# 20230822.net
KiCad netlist of a schematic drawn in EAGLE
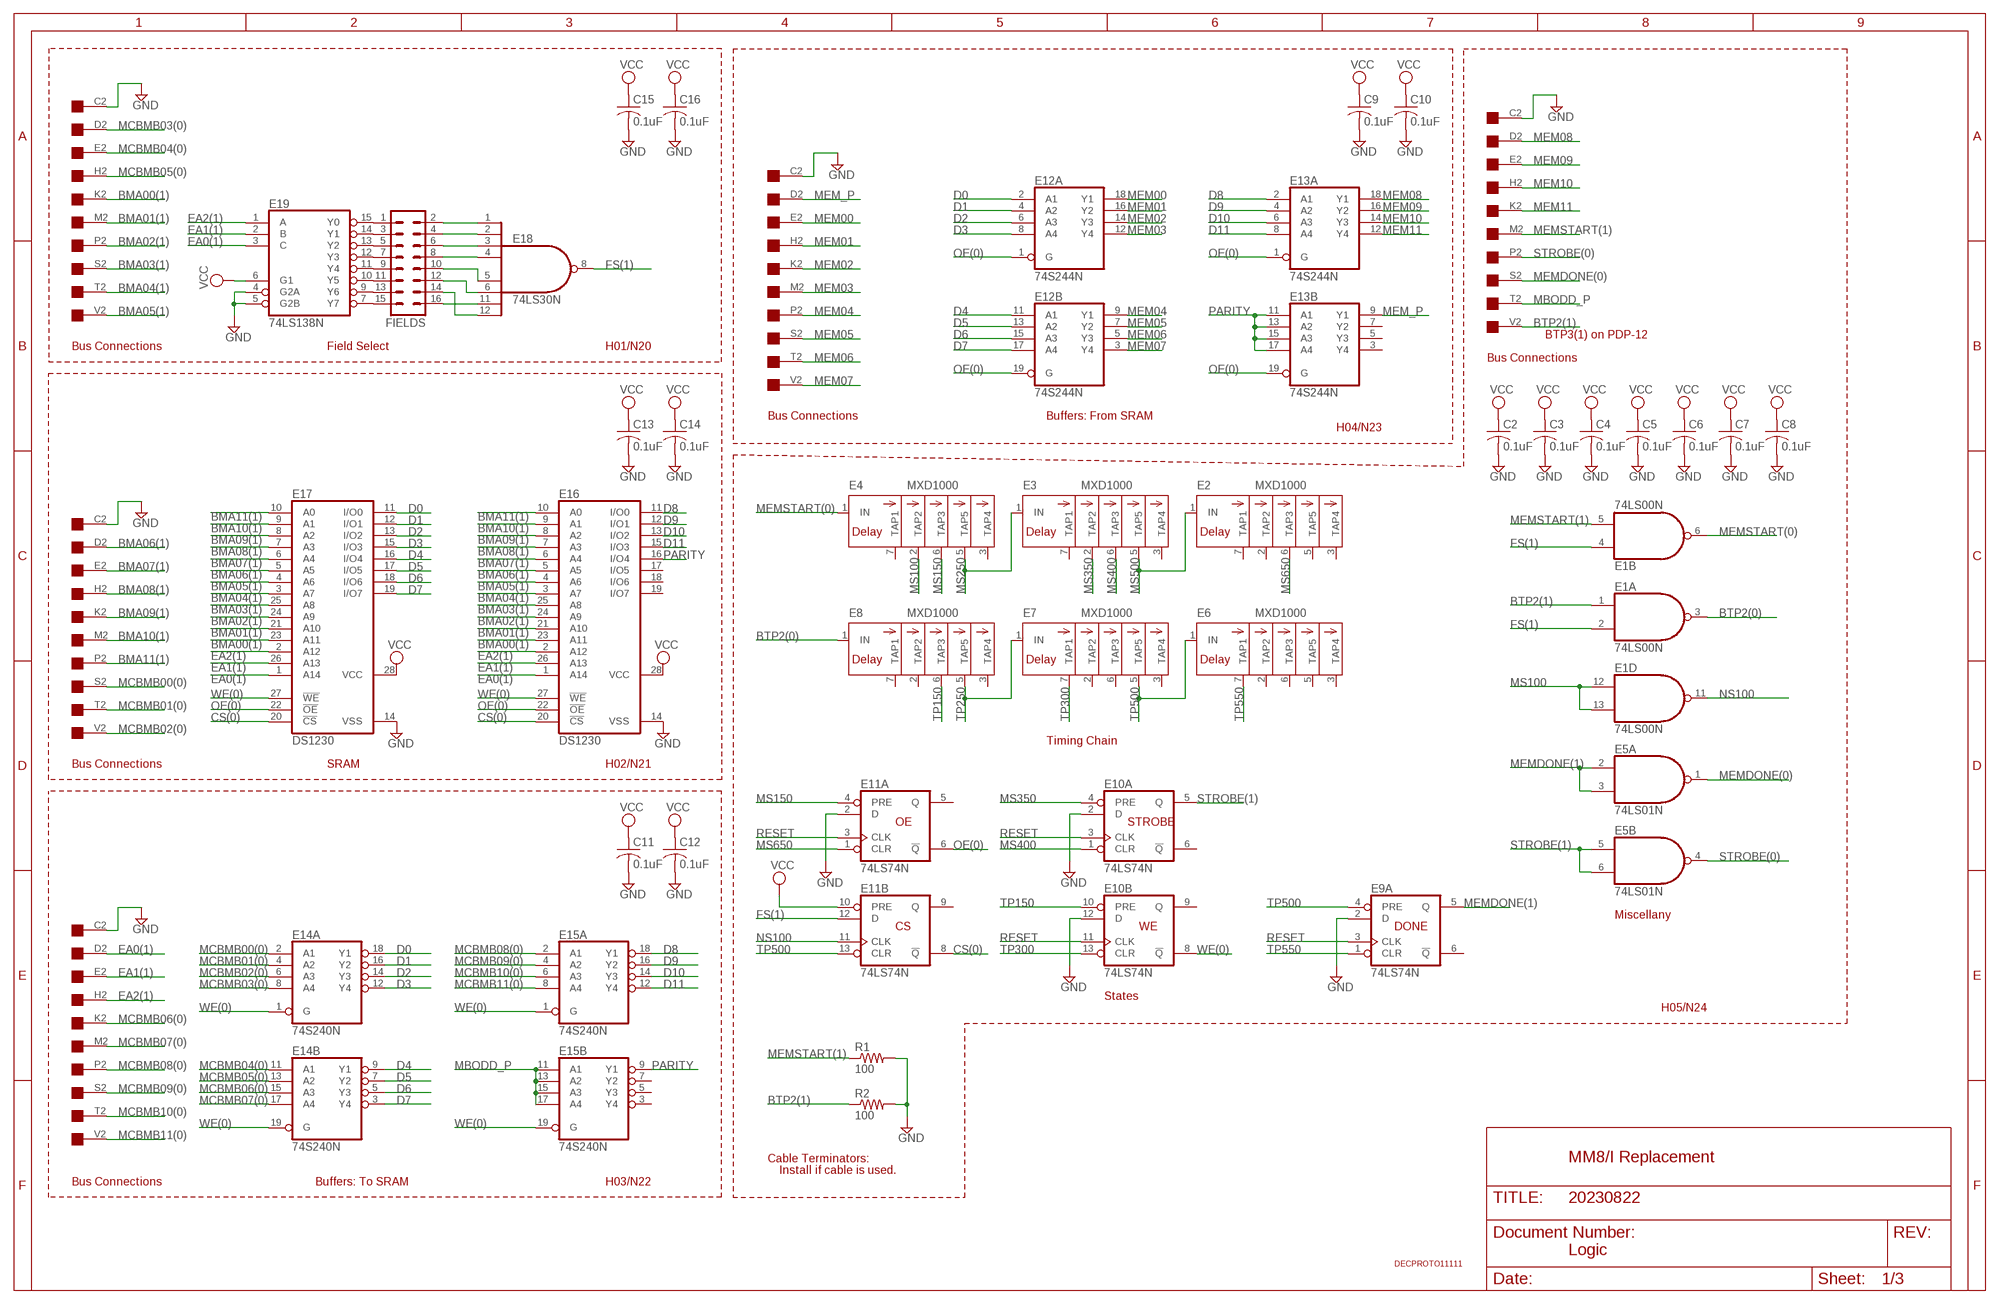
[diagram p0: schematic, sheet 1]
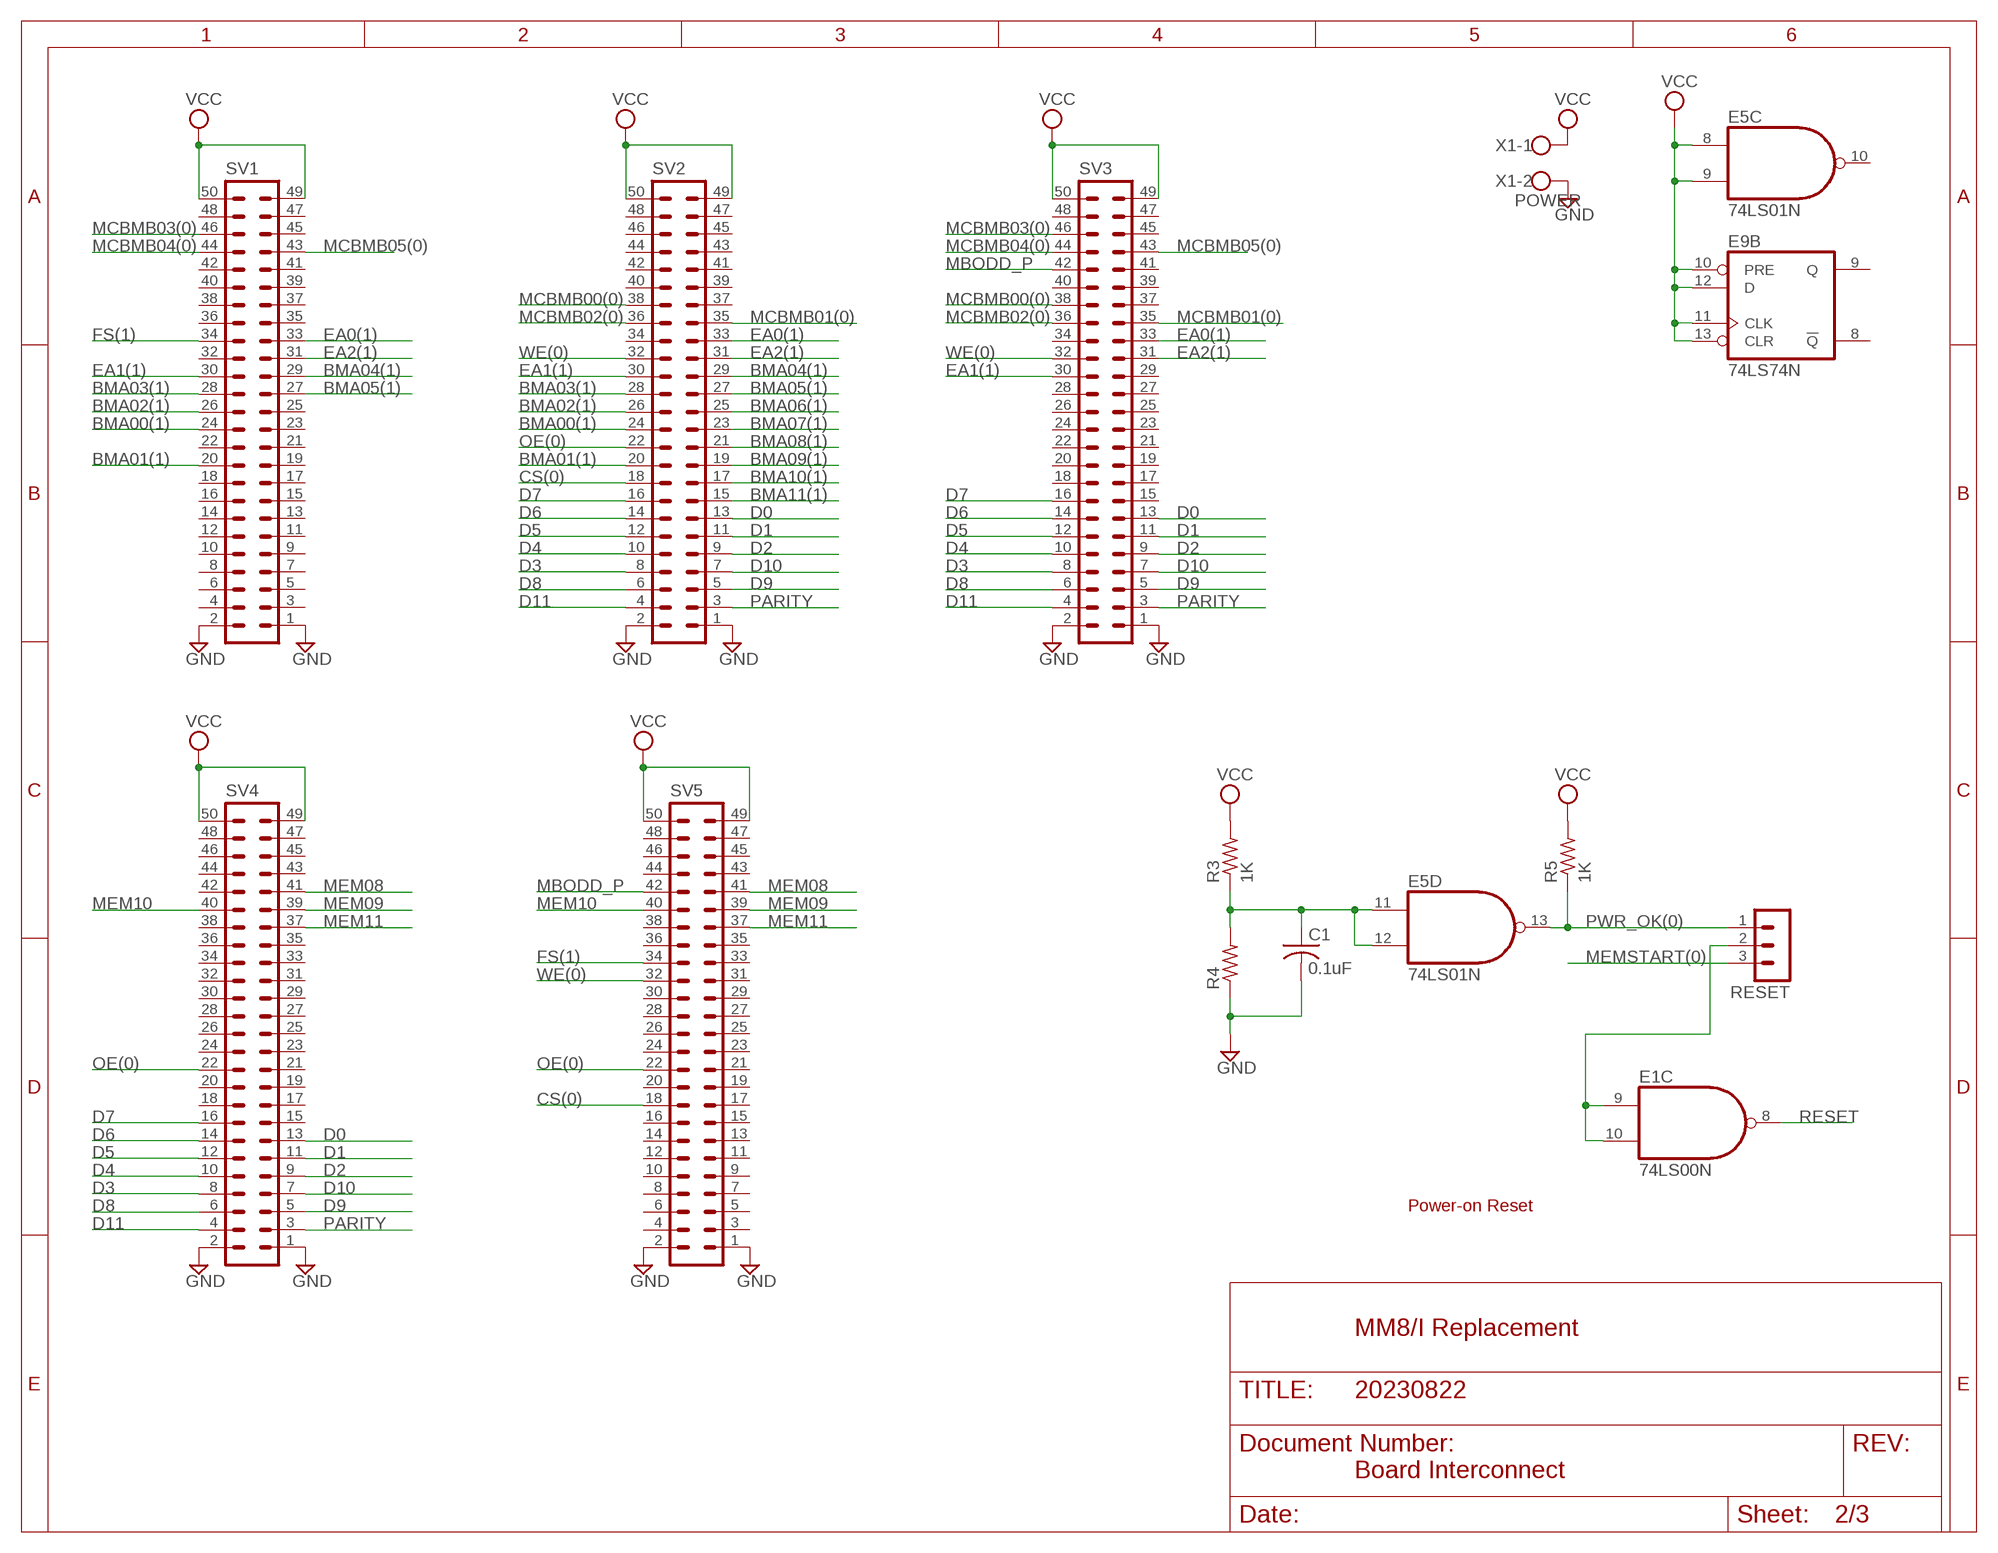
[diagram p1: schematic, sheet 2]
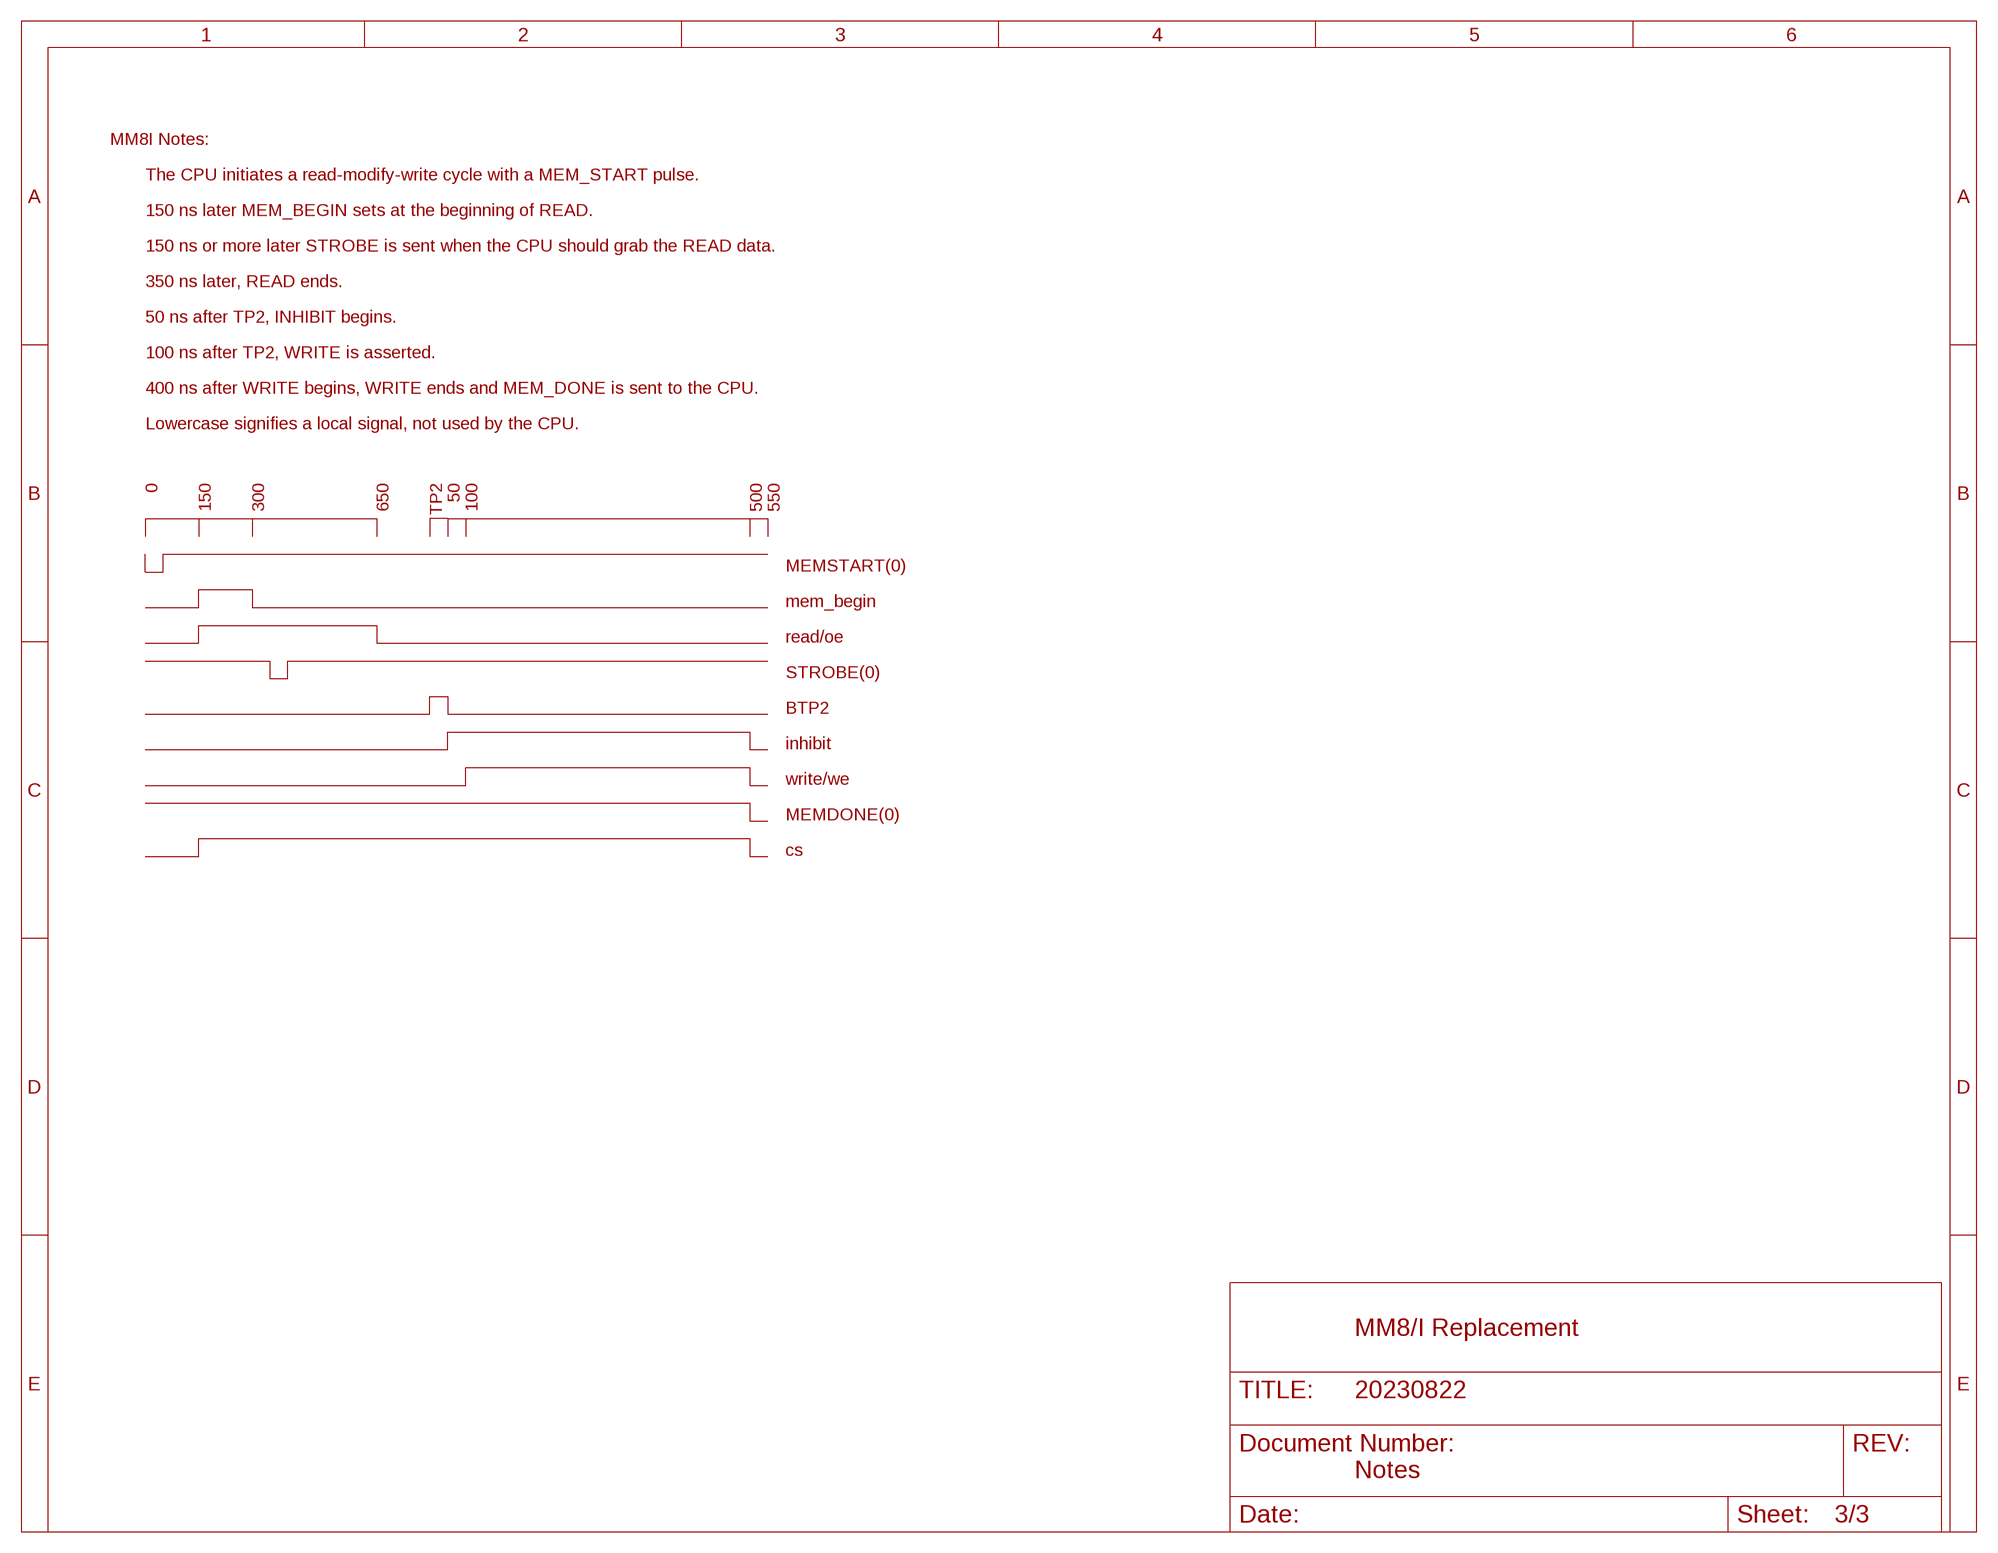
[diagram p2: schematic, sheet 3]

(export (version "E")
  (design (tool "Eeschema 10.0.6"))
  (components
    (comp (ref "C1")
      (value "0.1uF")
      (footprint "eagle-import:C050-025X075")
      (libsource (lib "eagle-import") (part "C-US050-025X075"))
    )
    (comp (ref "E1")
      (value "74LS00N")
      (footprint "eagle-import:DIL14")
      (libsource (lib "eagle-import") (part "7400NLS"))
    )
    (comp (ref "E5")
      (value "74LS01N")
      (footprint "eagle-import:DIL14")
      (libsource (lib "eagle-import") (part "7401NLS"))
    )
    (comp (ref "E9")
      (value "74LS74N")
      (footprint "eagle-import:DIL14")
      (libsource (lib "eagle-import") (part "7474NLS"))
    )
    (comp (ref "R3")
      (value "1K")
      (footprint "eagle-import:0207_10")
      (libsource (lib "eagle-import") (part "R-US_0207/10"))
    )
    (comp (ref "R4")
      (value "R-US_0207/10")
      (footprint "eagle-import:0207_10")
      (libsource (lib "eagle-import") (part "R-US_0207/10"))
    )
    (comp (ref "R5")
      (value "1K")
      (footprint "eagle-import:0207_10")
      (libsource (lib "eagle-import") (part "R-US_0207/10"))
    )
    (comp (ref "RESET")
      (value "MA03-1")
      (footprint "eagle-import:MA03-1")
      (libsource (lib "eagle-import") (part "MA03-1"))
    )
    (comp (ref "SV1")
      (value "ML50L")
      (footprint "eagle-import:ML50L")
      (libsource (lib "eagle-import") (part "ML50L"))
    )
    (comp (ref "SV2")
      (value "ML50L")
      (footprint "eagle-import:ML50L")
      (libsource (lib "eagle-import") (part "ML50L"))
    )
    (comp (ref "SV3")
      (value "ML50L")
      (footprint "eagle-import:ML50L")
      (libsource (lib "eagle-import") (part "ML50L"))
    )
    (comp (ref "SV4")
      (value "ML50L")
      (footprint "eagle-import:ML50L")
      (libsource (lib "eagle-import") (part "ML50L"))
    )
    (comp (ref "SV5")
      (value "ML50L")
      (footprint "eagle-import:ML50L")
      (libsource (lib "eagle-import") (part "ML50L"))
    )
    (comp (ref "X1")
      (value "POWER")
      (footprint "eagle-import:W237-102")
      (fields (field (name "MPN") "237-102"))
      (libsource (lib "eagle-import") (part "W237-102"))
    )
    (comp (ref "C2")
      (value "0.1uF")
      (footprint "eagle-import:C050-025X075")
      (libsource (lib "eagle-import") (part "C-US050-025X075"))
    )
    (comp (ref "C3")
      (value "0.1uF")
      (footprint "eagle-import:C050-025X075")
      (libsource (lib "eagle-import") (part "C-US050-025X075"))
    )
    (comp (ref "C4")
      (value "0.1uF")
      (footprint "eagle-import:C050-025X075")
      (libsource (lib "eagle-import") (part "C-US050-025X075"))
    )
    (comp (ref "C5")
      (value "0.1uF")
      (footprint "eagle-import:C050-025X075")
      (libsource (lib "eagle-import") (part "C-US050-025X075"))
    )
    (comp (ref "C6")
      (value "0.1uF")
      (footprint "eagle-import:C050-025X075")
      (libsource (lib "eagle-import") (part "C-US050-025X075"))
    )
    (comp (ref "C7")
      (value "0.1uF")
      (footprint "eagle-import:C050-025X075")
      (libsource (lib "eagle-import") (part "C-US050-025X075"))
    )
    (comp (ref "C8")
      (value "0.1uF")
      (footprint "eagle-import:C050-025X075")
      (libsource (lib "eagle-import") (part "C-US050-025X075"))
    )
    (comp (ref "C9")
      (value "0.1uF")
      (footprint "eagle-import:C050-025X075")
      (libsource (lib "eagle-import") (part "C-US050-025X075"))
    )
    (comp (ref "C10")
      (value "0.1uF")
      (footprint "eagle-import:C050-025X075")
      (libsource (lib "eagle-import") (part "C-US050-025X075"))
    )
    (comp (ref "C11")
      (value "0.1uF")
      (footprint "eagle-import:C050-025X075")
      (libsource (lib "eagle-import") (part "C-US050-025X075"))
    )
    (comp (ref "C12")
      (value "0.1uF")
      (footprint "eagle-import:C050-025X075")
      (libsource (lib "eagle-import") (part "C-US050-025X075"))
    )
    (comp (ref "C13")
      (value "0.1uF")
      (footprint "eagle-import:C050-025X075")
      (libsource (lib "eagle-import") (part "C-US050-025X075"))
    )
    (comp (ref "C14")
      (value "0.1uF")
      (footprint "eagle-import:C050-025X075")
      (libsource (lib "eagle-import") (part "C-US050-025X075"))
    )
    (comp (ref "C15")
      (value "0.1uF")
      (footprint "eagle-import:C050-025X075")
      (libsource (lib "eagle-import") (part "C-US050-025X075"))
    )
    (comp (ref "C16")
      (value "0.1uF")
      (footprint "eagle-import:C050-025X075")
      (libsource (lib "eagle-import") (part "C-US050-025X075"))
    )
    (comp (ref "E2")
      (value "MXD1000")
      (footprint "eagle-import:DIL08")
      (libsource (lib "eagle-import") (part "MXD1000"))
    )
    (comp (ref "E3")
      (value "MXD1000")
      (footprint "eagle-import:DIL08")
      (libsource (lib "eagle-import") (part "MXD1000"))
    )
    (comp (ref "E4")
      (value "MXD1000")
      (footprint "eagle-import:DIL08")
      (libsource (lib "eagle-import") (part "MXD1000"))
    )
    (comp (ref "E6")
      (value "MXD1000")
      (footprint "eagle-import:DIL08")
      (libsource (lib "eagle-import") (part "MXD1000"))
    )
    (comp (ref "E7")
      (value "MXD1000")
      (footprint "eagle-import:DIL08")
      (libsource (lib "eagle-import") (part "MXD1000"))
    )
    (comp (ref "E8")
      (value "MXD1000")
      (footprint "eagle-import:DIL08")
      (libsource (lib "eagle-import") (part "MXD1000"))
    )
    (comp (ref "E10")
      (value "74LS74N")
      (footprint "eagle-import:DIL14")
      (libsource (lib "eagle-import") (part "7474NLS"))
    )
    (comp (ref "E11")
      (value "74LS74N")
      (footprint "eagle-import:DIL14")
      (libsource (lib "eagle-import") (part "7474NLS"))
    )
    (comp (ref "E12")
      (value "74S244N")
      (footprint "eagle-import:DIL20")
      (libsource (lib "eagle-import") (part "74244NS"))
    )
    (comp (ref "E13")
      (value "74S244N")
      (footprint "eagle-import:DIL20")
      (libsource (lib "eagle-import") (part "74244NS"))
    )
    (comp (ref "E14")
      (value "74S240N")
      (footprint "eagle-import:DIL20")
      (libsource (lib "eagle-import") (part "74240NS"))
    )
    (comp (ref "E15")
      (value "74S240N")
      (footprint "eagle-import:DIL20")
      (libsource (lib "eagle-import") (part "74240NS"))
    )
    (comp (ref "E16")
      (value "DS1230")
      (footprint "eagle-import:DIL28-6")
      (libsource (lib "eagle-import") (part "62256P"))
    )
    (comp (ref "E17")
      (value "DS1230")
      (footprint "eagle-import:DIL28-6")
      (libsource (lib "eagle-import") (part "62256P"))
    )
    (comp (ref "E18")
      (value "74LS30N")
      (footprint "eagle-import:DIL14")
      (libsource (lib "eagle-import") (part "7430NLS"))
    )
    (comp (ref "E19")
      (value "74LS138N")
      (footprint "eagle-import:DIL16")
      (libsource (lib "eagle-import") (part "74138NLS"))
    )
    (comp (ref "FIELDS")
      (value "MA08-2")
      (footprint "eagle-import:MA08-2")
      (libsource (lib "eagle-import") (part "MA08-2"))
    )
    (comp (ref "H01")
      (value "EDGE-1")
      (footprint "eagle-import:EDGE-CON1")
      (libsource (lib "eagle-import") (part "EDGE-1"))
    )
    (comp (ref "H02")
      (value "EDGE-1")
      (footprint "eagle-import:EDGE-CON1")
      (libsource (lib "eagle-import") (part "EDGE-1"))
    )
    (comp (ref "H03")
      (value "EDGE-1")
      (footprint "eagle-import:EDGE-CON1")
      (libsource (lib "eagle-import") (part "EDGE-1"))
    )
    (comp (ref "H04")
      (value "EDGE-1")
      (footprint "eagle-import:EDGE-CON1")
      (libsource (lib "eagle-import") (part "EDGE-1"))
    )
    (comp (ref "H05")
      (value "EDGE-1")
      (footprint "eagle-import:EDGE-CON1")
      (libsource (lib "eagle-import") (part "EDGE-1"))
    )
    (comp (ref "R1")
      (value "100")
      (footprint "eagle-import:0207_10")
      (libsource (lib "eagle-import") (part "R-US_0207/10"))
    )
    (comp (ref "R2")
      (value "100")
      (footprint "eagle-import:0207_10")
      (libsource (lib "eagle-import") (part "R-US_0207/10"))
    )
    (comp (ref "U$6")
      (value "DECPROTO11111")
      (footprint "eagle-import:DECPROTO11111")
      (libsource (lib "eagle-import") (part "DECPROTO11111"))
    )
  )
  (nets
    (net (code "1") (name "BMA00(1)") (class "Default")
      (node (ref "E16") (pin "23") (pinfunction "A11_23") (pintype "input"))
      (node (ref "E17") (pin "23") (pinfunction "A11_23") (pintype "input"))
      (node (ref "H01") (pin "K2") (pinfunction "1_K2") (pintype "bidirectional"))
      (node (ref "SV1") (pin "24") (pinfunction "24_24") (pintype "passive"))
      (node (ref "SV2") (pin "24") (pinfunction "24_24") (pintype "passive"))
    )
    (net (code "2") (name "BMA01(1)") (class "Default")
      (node (ref "E16") (pin "21") (pinfunction "A10_21") (pintype "input"))
      (node (ref "E17") (pin "21") (pinfunction "A10_21") (pintype "input"))
      (node (ref "H01") (pin "M2") (pinfunction "1_M2") (pintype "bidirectional"))
      (node (ref "SV1") (pin "20") (pinfunction "20_20") (pintype "passive"))
      (node (ref "SV2") (pin "20") (pinfunction "20_20") (pintype "passive"))
    )
    (net (code "3") (name "BMA02(1)") (class "Default")
      (node (ref "E16") (pin "24") (pinfunction "A9_24") (pintype "input"))
      (node (ref "E17") (pin "24") (pinfunction "A9_24") (pintype "input"))
      (node (ref "H01") (pin "P2") (pinfunction "1_P2") (pintype "bidirectional"))
      (node (ref "SV1") (pin "26") (pinfunction "26_26") (pintype "passive"))
      (node (ref "SV2") (pin "26") (pinfunction "26_26") (pintype "passive"))
    )
    (net (code "4") (name "BMA03(1)") (class "Default")
      (node (ref "E16") (pin "25") (pinfunction "A8_25") (pintype "input"))
      (node (ref "E17") (pin "25") (pinfunction "A8_25") (pintype "input"))
      (node (ref "H01") (pin "S2") (pinfunction "1_S2") (pintype "bidirectional"))
      (node (ref "SV1") (pin "28") (pinfunction "28_28") (pintype "passive"))
      (node (ref "SV2") (pin "28") (pinfunction "28_28") (pintype "passive"))
    )
    (net (code "5") (name "BMA04(1)") (class "Default")
      (node (ref "E16") (pin "3") (pinfunction "A7_3") (pintype "input"))
      (node (ref "E17") (pin "3") (pinfunction "A7_3") (pintype "input"))
      (node (ref "H01") (pin "T2") (pinfunction "1_T2") (pintype "bidirectional"))
      (node (ref "SV1") (pin "29") (pinfunction "29_29") (pintype "passive"))
      (node (ref "SV2") (pin "29") (pinfunction "29_29") (pintype "passive"))
    )
    (net (code "6") (name "BMA05(1)") (class "Default")
      (node (ref "E16") (pin "4") (pinfunction "A6_4") (pintype "input"))
      (node (ref "E17") (pin "4") (pinfunction "A6_4") (pintype "input"))
      (node (ref "H01") (pin "V2") (pinfunction "1_V2") (pintype "bidirectional"))
      (node (ref "SV1") (pin "27") (pinfunction "27_27") (pintype "passive"))
      (node (ref "SV2") (pin "27") (pinfunction "27_27") (pintype "passive"))
    )
    (net (code "7") (name "BMA06(1)") (class "Default")
      (node (ref "E16") (pin "5") (pinfunction "A5_5") (pintype "input"))
      (node (ref "E17") (pin "5") (pinfunction "A5_5") (pintype "input"))
      (node (ref "H02") (pin "D2") (pinfunction "1_D2") (pintype "bidirectional"))
      (node (ref "SV2") (pin "25") (pinfunction "25_25") (pintype "passive"))
    )
    (net (code "8") (name "BMA07(1)") (class "Default")
      (node (ref "E16") (pin "6") (pinfunction "A4_6") (pintype "input"))
      (node (ref "E17") (pin "6") (pinfunction "A4_6") (pintype "input"))
      (node (ref "H02") (pin "E2") (pinfunction "1_E2") (pintype "bidirectional"))
      (node (ref "SV2") (pin "23") (pinfunction "23_23") (pintype "passive"))
    )
    (net (code "9") (name "BMA08(1)") (class "Default")
      (node (ref "E16") (pin "7") (pinfunction "A3_7") (pintype "input"))
      (node (ref "E17") (pin "7") (pinfunction "A3_7") (pintype "input"))
      (node (ref "H02") (pin "H2") (pinfunction "1_H2") (pintype "bidirectional"))
      (node (ref "SV2") (pin "21") (pinfunction "21_21") (pintype "passive"))
    )
    (net (code "10") (name "BMA09(1)") (class "Default")
      (node (ref "E16") (pin "8") (pinfunction "A2_8") (pintype "input"))
      (node (ref "E17") (pin "8") (pinfunction "A2_8") (pintype "input"))
      (node (ref "H02") (pin "K2") (pinfunction "1_K2") (pintype "bidirectional"))
      (node (ref "SV2") (pin "19") (pinfunction "19_19") (pintype "passive"))
    )
    (net (code "11") (name "BMA10(1)") (class "Default")
      (node (ref "E16") (pin "9") (pinfunction "A1_9") (pintype "input"))
      (node (ref "E17") (pin "9") (pinfunction "A1_9") (pintype "input"))
      (node (ref "H02") (pin "M2") (pinfunction "1_M2") (pintype "bidirectional"))
      (node (ref "SV2") (pin "17") (pinfunction "17_17") (pintype "passive"))
    )
    (net (code "12") (name "BMA11(1)") (class "Default")
      (node (ref "E16") (pin "10") (pinfunction "A0_10") (pintype "input"))
      (node (ref "E17") (pin "10") (pinfunction "A0_10") (pintype "input"))
      (node (ref "H02") (pin "P2") (pinfunction "1_P2") (pintype "bidirectional"))
      (node (ref "SV2") (pin "15") (pinfunction "15_15") (pintype "passive"))
    )
    (net (code "13") (name "BTP2(0)") (class "Default")
      (node (ref "E1") (pin "3") (pinfunction "O_3") (pintype "output"))
      (node (ref "E8") (pin "1") (pinfunction "IN_1") (pintype "input"))
    )
    (net (code "14") (name "BTP2(1)") (class "Default")
      (node (ref "E1") (pin "1") (pinfunction "I0_1") (pintype "input"))
      (node (ref "H05") (pin "V2") (pinfunction "1_V2") (pintype "bidirectional"))
      (node (ref "R2") (pin "1") (pinfunction "1_1") (pintype "passive"))
    )
    (net (code "15") (name "CS(0)") (class "Default")
      (node (ref "E11") (pin "8") (pinfunction "~{Q}_8") (pintype "output"))
      (node (ref "E16") (pin "20") (pinfunction "~{CS}_20") (pintype "input"))
      (node (ref "E17") (pin "20") (pinfunction "~{CS}_20") (pintype "input"))
      (node (ref "SV2") (pin "18") (pinfunction "18_18") (pintype "passive"))
      (node (ref "SV5") (pin "18") (pinfunction "18_18") (pintype "passive"))
    )
    (net (code "16") (name "D0") (class "Default")
      (node (ref "E12") (pin "2") (pinfunction "A1_2") (pintype "input"))
      (node (ref "E14") (pin "18") (pinfunction "Y1_18") (pintype "tri_state"))
      (node (ref "E17") (pin "11") (pinfunction "I/O0_11") (pintype "bidirectional"))
      (node (ref "SV2") (pin "13") (pinfunction "13_13") (pintype "passive"))
      (node (ref "SV3") (pin "13") (pinfunction "13_13") (pintype "passive"))
      (node (ref "SV4") (pin "13") (pinfunction "13_13") (pintype "passive"))
    )
    (net (code "17") (name "D1") (class "Default")
      (node (ref "E12") (pin "4") (pinfunction "A2_4") (pintype "input"))
      (node (ref "E14") (pin "16") (pinfunction "Y2_16") (pintype "tri_state"))
      (node (ref "E17") (pin "12") (pinfunction "I/O1_12") (pintype "bidirectional"))
      (node (ref "SV2") (pin "11") (pinfunction "11_11") (pintype "passive"))
      (node (ref "SV3") (pin "11") (pinfunction "11_11") (pintype "passive"))
      (node (ref "SV4") (pin "11") (pinfunction "11_11") (pintype "passive"))
    )
    (net (code "18") (name "D2") (class "Default")
      (node (ref "E12") (pin "6") (pinfunction "A3_6") (pintype "input"))
      (node (ref "E14") (pin "14") (pinfunction "Y3_14") (pintype "tri_state"))
      (node (ref "E17") (pin "13") (pinfunction "I/O2_13") (pintype "bidirectional"))
      (node (ref "SV2") (pin "9") (pinfunction "9_9") (pintype "passive"))
      (node (ref "SV3") (pin "9") (pinfunction "9_9") (pintype "passive"))
      (node (ref "SV4") (pin "9") (pinfunction "9_9") (pintype "passive"))
    )
    (net (code "19") (name "D3") (class "Default")
      (node (ref "E12") (pin "8") (pinfunction "A4_8") (pintype "input"))
      (node (ref "E14") (pin "12") (pinfunction "Y4_12") (pintype "tri_state"))
      (node (ref "E17") (pin "15") (pinfunction "I/O3_15") (pintype "bidirectional"))
      (node (ref "SV2") (pin "8") (pinfunction "8_8") (pintype "passive"))
      (node (ref "SV3") (pin "8") (pinfunction "8_8") (pintype "passive"))
      (node (ref "SV4") (pin "8") (pinfunction "8_8") (pintype "passive"))
    )
    (net (code "20") (name "D4") (class "Default")
      (node (ref "E12") (pin "11") (pinfunction "A1_11") (pintype "input"))
      (node (ref "E14") (pin "9") (pinfunction "Y1_9") (pintype "tri_state"))
      (node (ref "E17") (pin "16") (pinfunction "I/O4_16") (pintype "bidirectional"))
      (node (ref "SV2") (pin "10") (pinfunction "10_10") (pintype "passive"))
      (node (ref "SV3") (pin "10") (pinfunction "10_10") (pintype "passive"))
      (node (ref "SV4") (pin "10") (pinfunction "10_10") (pintype "passive"))
    )
    (net (code "21") (name "D5") (class "Default")
      (node (ref "E12") (pin "13") (pinfunction "A2_13") (pintype "input"))
      (node (ref "E14") (pin "7") (pinfunction "Y2_7") (pintype "tri_state"))
      (node (ref "E17") (pin "17") (pinfunction "I/O5_17") (pintype "bidirectional"))
      (node (ref "SV2") (pin "12") (pinfunction "12_12") (pintype "passive"))
      (node (ref "SV3") (pin "12") (pinfunction "12_12") (pintype "passive"))
      (node (ref "SV4") (pin "12") (pinfunction "12_12") (pintype "passive"))
    )
    (net (code "22") (name "D6") (class "Default")
      (node (ref "E12") (pin "15") (pinfunction "A3_15") (pintype "input"))
      (node (ref "E14") (pin "5") (pinfunction "Y3_5") (pintype "tri_state"))
      (node (ref "E17") (pin "18") (pinfunction "I/O6_18") (pintype "bidirectional"))
      (node (ref "SV2") (pin "14") (pinfunction "14_14") (pintype "passive"))
      (node (ref "SV3") (pin "14") (pinfunction "14_14") (pintype "passive"))
      (node (ref "SV4") (pin "14") (pinfunction "14_14") (pintype "passive"))
    )
    (net (code "23") (name "D7") (class "Default")
      (node (ref "E12") (pin "17") (pinfunction "A4_17") (pintype "input"))
      (node (ref "E14") (pin "3") (pinfunction "Y4_3") (pintype "tri_state"))
      (node (ref "E17") (pin "19") (pinfunction "I/O7_19") (pintype "bidirectional"))
      (node (ref "SV2") (pin "16") (pinfunction "16_16") (pintype "passive"))
      (node (ref "SV3") (pin "16") (pinfunction "16_16") (pintype "passive"))
      (node (ref "SV4") (pin "16") (pinfunction "16_16") (pintype "passive"))
    )
    (net (code "24") (name "D8") (class "Default")
      (node (ref "E13") (pin "2") (pinfunction "A1_2") (pintype "input"))
      (node (ref "E15") (pin "18") (pinfunction "Y1_18") (pintype "tri_state"))
      (node (ref "E16") (pin "11") (pinfunction "I/O0_11") (pintype "bidirectional"))
      (node (ref "SV2") (pin "6") (pinfunction "6_6") (pintype "passive"))
      (node (ref "SV3") (pin "6") (pinfunction "6_6") (pintype "passive"))
      (node (ref "SV4") (pin "6") (pinfunction "6_6") (pintype "passive"))
    )
    (net (code "25") (name "D9") (class "Default")
      (node (ref "E13") (pin "4") (pinfunction "A2_4") (pintype "input"))
      (node (ref "E15") (pin "16") (pinfunction "Y2_16") (pintype "tri_state"))
      (node (ref "E16") (pin "12") (pinfunction "I/O1_12") (pintype "bidirectional"))
      (node (ref "SV2") (pin "5") (pinfunction "5_5") (pintype "passive"))
      (node (ref "SV3") (pin "5") (pinfunction "5_5") (pintype "passive"))
      (node (ref "SV4") (pin "5") (pinfunction "5_5") (pintype "passive"))
    )
    (net (code "26") (name "D10") (class "Default")
      (node (ref "E13") (pin "6") (pinfunction "A3_6") (pintype "input"))
      (node (ref "E15") (pin "14") (pinfunction "Y3_14") (pintype "tri_state"))
      (node (ref "E16") (pin "13") (pinfunction "I/O2_13") (pintype "bidirectional"))
      (node (ref "SV2") (pin "7") (pinfunction "7_7") (pintype "passive"))
      (node (ref "SV3") (pin "7") (pinfunction "7_7") (pintype "passive"))
      (node (ref "SV4") (pin "7") (pinfunction "7_7") (pintype "passive"))
    )
    (net (code "27") (name "D11") (class "Default")
      (node (ref "E13") (pin "8") (pinfunction "A4_8") (pintype "input"))
      (node (ref "E15") (pin "12") (pinfunction "Y4_12") (pintype "tri_state"))
      (node (ref "E16") (pin "15") (pinfunction "I/O3_15") (pintype "bidirectional"))
      (node (ref "SV2") (pin "4") (pinfunction "4_4") (pintype "passive"))
      (node (ref "SV3") (pin "4") (pinfunction "4_4") (pintype "passive"))
      (node (ref "SV4") (pin "4") (pinfunction "4_4") (pintype "passive"))
    )
    (net (code "28") (name "EA0(1)") (class "Default")
      (node (ref "E16") (pin "1") (pinfunction "A14_1") (pintype "input"))
      (node (ref "E17") (pin "1") (pinfunction "A14_1") (pintype "input"))
      (node (ref "E19") (pin "3") (pinfunction "C_3") (pintype "input"))
      (node (ref "H03") (pin "D2") (pinfunction "1_D2") (pintype "bidirectional"))
      (node (ref "SV1") (pin "33") (pinfunction "33_33") (pintype "passive"))
      (node (ref "SV2") (pin "33") (pinfunction "33_33") (pintype "passive"))
      (node (ref "SV3") (pin "33") (pinfunction "33_33") (pintype "passive"))
    )
    (net (code "29") (name "EA1(1)") (class "Default")
      (node (ref "E16") (pin "26") (pinfunction "A13_26") (pintype "input"))
      (node (ref "E17") (pin "26") (pinfunction "A13_26") (pintype "input"))
      (node (ref "E19") (pin "2") (pinfunction "B_2") (pintype "input"))
      (node (ref "H03") (pin "E2") (pinfunction "1_E2") (pintype "bidirectional"))
      (node (ref "SV1") (pin "30") (pinfunction "30_30") (pintype "passive"))
      (node (ref "SV2") (pin "30") (pinfunction "30_30") (pintype "passive"))
      (node (ref "SV3") (pin "30") (pinfunction "30_30") (pintype "passive"))
    )
    (net (code "30") (name "EA2(1)") (class "Default")
      (node (ref "E16") (pin "2") (pinfunction "A12_2") (pintype "input"))
      (node (ref "E17") (pin "2") (pinfunction "A12_2") (pintype "input"))
      (node (ref "E19") (pin "1") (pinfunction "A_1") (pintype "input"))
      (node (ref "H03") (pin "H2") (pinfunction "1_H2") (pintype "bidirectional"))
      (node (ref "SV1") (pin "31") (pinfunction "31_31") (pintype "passive"))
      (node (ref "SV2") (pin "31") (pinfunction "31_31") (pintype "passive"))
      (node (ref "SV3") (pin "31") (pinfunction "31_31") (pintype "passive"))
    )
    (net (code "31") (name "FS(1)") (class "Default")
      (node (ref "E1") (pin "2") (pinfunction "I1_2") (pintype "input"))
      (node (ref "E1") (pin "4") (pinfunction "I0_4") (pintype "input"))
      (node (ref "E11") (pin "12") (pinfunction "D_12") (pintype "input"))
      (node (ref "E18") (pin "8") (pinfunction "O_8") (pintype "output"))
      (node (ref "SV1") (pin "34") (pinfunction "34_34") (pintype "passive"))
      (node (ref "SV5") (pin "34") (pinfunction "34_34") (pintype "passive"))
    )
    (net (code "32") (name "GND") (class "Default")
      (node (ref "C1") (pin "2") (pinfunction "2_2") (pintype "passive"))
      (node (ref "C10") (pin "2") (pinfunction "2_2") (pintype "passive"))
      (node (ref "C11") (pin "2") (pinfunction "2_2") (pintype "passive"))
      (node (ref "C12") (pin "2") (pinfunction "2_2") (pintype "passive"))
      (node (ref "C13") (pin "2") (pinfunction "2_2") (pintype "passive"))
      (node (ref "C14") (pin "2") (pinfunction "2_2") (pintype "passive"))
      (node (ref "C15") (pin "2") (pinfunction "2_2") (pintype "passive"))
      (node (ref "C16") (pin "2") (pinfunction "2_2") (pintype "passive"))
      (node (ref "C2") (pin "2") (pinfunction "2_2") (pintype "passive"))
      (node (ref "C3") (pin "2") (pinfunction "2_2") (pintype "passive"))
      (node (ref "C4") (pin "2") (pinfunction "2_2") (pintype "passive"))
      (node (ref "C5") (pin "2") (pinfunction "2_2") (pintype "passive"))
      (node (ref "C6") (pin "2") (pinfunction "2_2") (pintype "passive"))
      (node (ref "C7") (pin "2") (pinfunction "2_2") (pintype "passive"))
      (node (ref "C8") (pin "2") (pinfunction "2_2") (pintype "passive"))
      (node (ref "C9") (pin "2") (pinfunction "2_2") (pintype "passive"))
      (node (ref "E10") (pin "12") (pinfunction "D_12") (pintype "input"))
      (node (ref "E10") (pin "2") (pinfunction "D_2") (pintype "input"))
      (node (ref "E11") (pin "2") (pinfunction "D_2") (pintype "input"))
      (node (ref "E16") (pin "14") (pinfunction "VSS_14") (pintype "power_in"))
      (node (ref "E17") (pin "14") (pinfunction "VSS_14") (pintype "power_in"))
      (node (ref "E19") (pin "4") (pinfunction "G2A_4") (pintype "input"))
      (node (ref "E19") (pin "5") (pinfunction "G2B_5") (pintype "input"))
      (node (ref "E9") (pin "2") (pinfunction "D_2") (pintype "input"))
      (node (ref "H01") (pin "C2") (pinfunction "1_C2") (pintype "bidirectional"))
      (node (ref "H02") (pin "C2") (pinfunction "1_C2") (pintype "bidirectional"))
      (node (ref "H03") (pin "C2") (pinfunction "1_C2") (pintype "bidirectional"))
      (node (ref "H04") (pin "C2") (pinfunction "1_C2") (pintype "bidirectional"))
      (node (ref "H05") (pin "C2") (pinfunction "1_C2") (pintype "bidirectional"))
      (node (ref "R1") (pin "2") (pinfunction "2_2") (pintype "passive"))
      (node (ref "R2") (pin "2") (pinfunction "2_2") (pintype "passive"))
      (node (ref "R4") (pin "1") (pinfunction "1_1") (pintype "passive"))
      (node (ref "SV1") (pin "1") (pinfunction "1_1") (pintype "passive"))
      (node (ref "SV1") (pin "2") (pinfunction "2_2") (pintype "passive"))
      (node (ref "SV2") (pin "1") (pinfunction "1_1") (pintype "passive"))
      (node (ref "SV2") (pin "2") (pinfunction "2_2") (pintype "passive"))
      (node (ref "SV3") (pin "1") (pinfunction "1_1") (pintype "passive"))
      (node (ref "SV3") (pin "2") (pinfunction "2_2") (pintype "passive"))
      (node (ref "SV4") (pin "1") (pinfunction "1_1") (pintype "passive"))
      (node (ref "SV4") (pin "2") (pinfunction "2_2") (pintype "passive"))
      (node (ref "SV5") (pin "1") (pinfunction "1_1") (pintype "passive"))
      (node (ref "SV5") (pin "2") (pinfunction "2_2") (pintype "passive"))
      (node (ref "X1") (pin "2") (pinfunction "KL_2") (pintype "passive"))
    )
    (net (code "33") (name "MBODD_P") (class "Default")
      (node (ref "E15") (pin "11") (pinfunction "A1_11") (pintype "input"))
      (node (ref "E15") (pin "13") (pinfunction "A2_13") (pintype "input"))
      (node (ref "E15") (pin "15") (pinfunction "A3_15") (pintype "input"))
      (node (ref "E15") (pin "17") (pinfunction "A4_17") (pintype "input"))
      (node (ref "H05") (pin "T2") (pinfunction "1_T2") (pintype "bidirectional"))
      (node (ref "SV3") (pin "42") (pinfunction "42_42") (pintype "passive"))
      (node (ref "SV5") (pin "42") (pinfunction "42_42") (pintype "passive"))
    )
    (net (code "34") (name "MCBMB00(0)") (class "Default")
      (node (ref "E14") (pin "2") (pinfunction "A1_2") (pintype "input"))
      (node (ref "H02") (pin "S2") (pinfunction "1_S2") (pintype "bidirectional"))
      (node (ref "SV2") (pin "38") (pinfunction "38_38") (pintype "passive"))
      (node (ref "SV3") (pin "38") (pinfunction "38_38") (pintype "passive"))
    )
    (net (code "35") (name "MCBMB01(0)") (class "Default")
      (node (ref "E14") (pin "4") (pinfunction "A2_4") (pintype "input"))
      (node (ref "H02") (pin "T2") (pinfunction "1_T2") (pintype "bidirectional"))
      (node (ref "SV2") (pin "35") (pinfunction "35_35") (pintype "passive"))
      (node (ref "SV3") (pin "35") (pinfunction "35_35") (pintype "passive"))
    )
    (net (code "36") (name "MCBMB02(0)") (class "Default")
      (node (ref "E14") (pin "6") (pinfunction "A3_6") (pintype "input"))
      (node (ref "H02") (pin "V2") (pinfunction "1_V2") (pintype "bidirectional"))
      (node (ref "SV2") (pin "36") (pinfunction "36_36") (pintype "passive"))
      (node (ref "SV3") (pin "36") (pinfunction "36_36") (pintype "passive"))
    )
    (net (code "37") (name "MCBMB03(0)") (class "Default")
      (node (ref "E14") (pin "8") (pinfunction "A4_8") (pintype "input"))
      (node (ref "H01") (pin "D2") (pinfunction "1_D2") (pintype "bidirectional"))
      (node (ref "SV1") (pin "46") (pinfunction "46_46") (pintype "passive"))
      (node (ref "SV3") (pin "46") (pinfunction "46_46") (pintype "passive"))
    )
    (net (code "38") (name "MCBMB04(0)") (class "Default")
      (node (ref "E14") (pin "11") (pinfunction "A1_11") (pintype "input"))
      (node (ref "H01") (pin "E2") (pinfunction "1_E2") (pintype "bidirectional"))
      (node (ref "SV1") (pin "44") (pinfunction "44_44") (pintype "passive"))
      (node (ref "SV3") (pin "44") (pinfunction "44_44") (pintype "passive"))
    )
    (net (code "39") (name "MCBMB05(0)") (class "Default")
      (node (ref "E14") (pin "13") (pinfunction "A2_13") (pintype "input"))
      (node (ref "H01") (pin "H2") (pinfunction "1_H2") (pintype "bidirectional"))
      (node (ref "SV1") (pin "43") (pinfunction "43_43") (pintype "passive"))
      (node (ref "SV3") (pin "43") (pinfunction "43_43") (pintype "passive"))
    )
    (net (code "40") (name "MCBMB06(0)") (class "Default")
      (node (ref "E14") (pin "15") (pinfunction "A3_15") (pintype "input"))
      (node (ref "H03") (pin "K2") (pinfunction "1_K2") (pintype "bidirectional"))
    )
    (net (code "41") (name "MCBMB07(0)") (class "Default")
      (node (ref "E14") (pin "17") (pinfunction "A4_17") (pintype "input"))
      (node (ref "H03") (pin "M2") (pinfunction "1_M2") (pintype "bidirectional"))
    )
    (net (code "42") (name "MCBMB08(0)") (class "Default")
      (node (ref "E15") (pin "2") (pinfunction "A1_2") (pintype "input"))
      (node (ref "H03") (pin "P2") (pinfunction "1_P2") (pintype "bidirectional"))
    )
    (net (code "43") (name "MCBMB09(0)") (class "Default")
      (node (ref "E15") (pin "4") (pinfunction "A2_4") (pintype "input"))
      (node (ref "H03") (pin "S2") (pinfunction "1_S2") (pintype "bidirectional"))
    )
    (net (code "44") (name "MCBMB10(0)") (class "Default")
      (node (ref "E15") (pin "6") (pinfunction "A3_6") (pintype "input"))
      (node (ref "H03") (pin "T2") (pinfunction "1_T2") (pintype "bidirectional"))
    )
    (net (code "45") (name "MCBMB11(0)") (class "Default")
      (node (ref "E15") (pin "8") (pinfunction "A4_8") (pintype "input"))
      (node (ref "H03") (pin "V2") (pinfunction "1_V2") (pintype "bidirectional"))
    )
    (net (code "46") (name "MEM00") (class "Default")
      (node (ref "E12") (pin "18") (pinfunction "Y1_18") (pintype "tri_state"))
      (node (ref "H04") (pin "E2") (pinfunction "1_E2") (pintype "bidirectional"))
    )
    (net (code "47") (name "MEM01") (class "Default")
      (node (ref "E12") (pin "16") (pinfunction "Y2_16") (pintype "tri_state"))
      (node (ref "H04") (pin "H2") (pinfunction "1_H2") (pintype "bidirectional"))
    )
    (net (code "48") (name "MEM02") (class "Default")
      (node (ref "E12") (pin "14") (pinfunction "Y3_14") (pintype "tri_state"))
      (node (ref "H04") (pin "K2") (pinfunction "1_K2") (pintype "bidirectional"))
    )
    (net (code "49") (name "MEM03") (class "Default")
      (node (ref "E12") (pin "12") (pinfunction "Y4_12") (pintype "tri_state"))
      (node (ref "H04") (pin "M2") (pinfunction "1_M2") (pintype "bidirectional"))
    )
    (net (code "50") (name "MEM04") (class "Default")
      (node (ref "E12") (pin "9") (pinfunction "Y1_9") (pintype "tri_state"))
      (node (ref "H04") (pin "P2") (pinfunction "1_P2") (pintype "bidirectional"))
    )
    (net (code "51") (name "MEM05") (class "Default")
      (node (ref "E12") (pin "7") (pinfunction "Y2_7") (pintype "tri_state"))
      (node (ref "H04") (pin "S2") (pinfunction "1_S2") (pintype "bidirectional"))
    )
    (net (code "52") (name "MEM06") (class "Default")
      (node (ref "E12") (pin "5") (pinfunction "Y3_5") (pintype "tri_state"))
      (node (ref "H04") (pin "T2") (pinfunction "1_T2") (pintype "bidirectional"))
    )
    (net (code "53") (name "MEM07") (class "Default")
      (node (ref "E12") (pin "3") (pinfunction "Y4_3") (pintype "tri_state"))
      (node (ref "H04") (pin "V2") (pinfunction "1_V2") (pintype "bidirectional"))
    )
    (net (code "54") (name "MEM08") (class "Default")
      (node (ref "E13") (pin "18") (pinfunction "Y1_18") (pintype "tri_state"))
      (node (ref "H05") (pin "D2") (pinfunction "1_D2") (pintype "bidirectional"))
      (node (ref "SV4") (pin "41") (pinfunction "41_41") (pintype "passive"))
      (node (ref "SV5") (pin "41") (pinfunction "41_41") (pintype "passive"))
    )
    (net (code "55") (name "MEM09") (class "Default")
      (node (ref "E13") (pin "16") (pinfunction "Y2_16") (pintype "tri_state"))
      (node (ref "H05") (pin "E2") (pinfunction "1_E2") (pintype "bidirectional"))
      (node (ref "SV4") (pin "39") (pinfunction "39_39") (pintype "passive"))
      (node (ref "SV5") (pin "39") (pinfunction "39_39") (pintype "passive"))
    )
    (net (code "56") (name "MEM10") (class "Default")
      (node (ref "E13") (pin "14") (pinfunction "Y3_14") (pintype "tri_state"))
      (node (ref "H05") (pin "H2") (pinfunction "1_H2") (pintype "bidirectional"))
      (node (ref "SV4") (pin "40") (pinfunction "40_40") (pintype "passive"))
      (node (ref "SV5") (pin "40") (pinfunction "40_40") (pintype "passive"))
    )
    (net (code "57") (name "MEM11") (class "Default")
      (node (ref "E13") (pin "12") (pinfunction "Y4_12") (pintype "tri_state"))
      (node (ref "H05") (pin "K2") (pinfunction "1_K2") (pintype "bidirectional"))
      (node (ref "SV4") (pin "37") (pinfunction "37_37") (pintype "passive"))
      (node (ref "SV5") (pin "37") (pinfunction "37_37") (pintype "passive"))
    )
    (net (code "58") (name "MEMDONE(0)") (class "Default")
      (node (ref "E5") (pin "1") (pinfunction "O_1") (pintype "open_collector"))
      (node (ref "H05") (pin "S2") (pinfunction "1_S2") (pintype "bidirectional"))
    )
    (net (code "59") (name "MEMDONE(1)") (class "Default")
      (node (ref "E5") (pin "2") (pinfunction "I0_2") (pintype "input"))
      (node (ref "E5") (pin "3") (pinfunction "I1_3") (pintype "input"))
      (node (ref "E9") (pin "5") (pinfunction "Q_5") (pintype "output"))
    )
    (net (code "60") (name "MEMSTART(0)") (class "Default")
      (node (ref "E1") (pin "6") (pinfunction "O_6") (pintype "output"))
      (node (ref "E4") (pin "1") (pinfunction "IN_1") (pintype "input"))
      (node (ref "RESET") (pin "3") (pinfunction "3_3") (pintype "passive"))
    )
    (net (code "61") (name "MEMSTART(1)") (class "Default")
      (node (ref "E1") (pin "5") (pinfunction "I1_5") (pintype "input"))
      (node (ref "H05") (pin "M2") (pinfunction "1_M2") (pintype "bidirectional"))
      (node (ref "R1") (pin "1") (pinfunction "1_1") (pintype "passive"))
    )
    (net (code "62") (name "MEM_P") (class "Default")
      (node (ref "E13") (pin "9") (pinfunction "Y1_9") (pintype "tri_state"))
      (node (ref "H04") (pin "D2") (pinfunction "1_D2") (pintype "bidirectional"))
    )
    (net (code "63") (name "MS100") (class "Default")
      (node (ref "E1") (pin "12") (pinfunction "I0_12") (pintype "input"))
      (node (ref "E1") (pin "13") (pinfunction "I1_13") (pintype "input"))
      (node (ref "E4") (pin "2") (pinfunction "TAP2_2") (pintype "output"))
    )
    (net (code "64") (name "MS150") (class "Default")
      (node (ref "E11") (pin "4") (pinfunction "PRE_4") (pintype "input"))
      (node (ref "E4") (pin "6") (pinfunction "TAP3_6") (pintype "output"))
    )
    (net (code "65") (name "MS250") (class "Default")
      (node (ref "E3") (pin "1") (pinfunction "IN_1") (pintype "input"))
      (node (ref "E4") (pin "5") (pinfunction "TAP5_5") (pintype "output"))
    )
    (net (code "66") (name "MS350") (class "Default")
      (node (ref "E10") (pin "4") (pinfunction "PRE_4") (pintype "input"))
      (node (ref "E3") (pin "2") (pinfunction "TAP2_2") (pintype "output"))
    )
    (net (code "67") (name "MS400") (class "Default")
      (node (ref "E10") (pin "1") (pinfunction "CLR_1") (pintype "input"))
      (node (ref "E3") (pin "6") (pinfunction "TAP3_6") (pintype "output"))
    )
    (net (code "68") (name "MS500") (class "Default")
      (node (ref "E2") (pin "1") (pinfunction "IN_1") (pintype "input"))
      (node (ref "E3") (pin "5") (pinfunction "TAP5_5") (pintype "output"))
    )
    (net (code "69") (name "MS650") (class "Default")
      (node (ref "E11") (pin "1") (pinfunction "CLR_1") (pintype "input"))
      (node (ref "E2") (pin "6") (pinfunction "TAP3_6") (pintype "output"))
    )
    (net (code "70") (name "NS100") (class "Default")
      (node (ref "E1") (pin "11") (pinfunction "O_11") (pintype "output"))
      (node (ref "E11") (pin "11") (pinfunction "CLK_11") (pintype "input"))
    )
    (net (code "71") (name "Net-(E1C-I0)") (class "Default")
      (node (ref "E1") (pin "10") (pinfunction "I1_10") (pintype "input"))
      (node (ref "E1") (pin "9") (pinfunction "I0_9") (pintype "input"))
      (node (ref "RESET") (pin "2") (pinfunction "2_2") (pintype "passive"))
    )
    (net (code "72") (name "Net-(E5D-I0)") (class "Default")
      (node (ref "C1") (pin "1") (pinfunction "1_1") (pintype "passive"))
      (node (ref "E5") (pin "11") (pinfunction "I0_11") (pintype "input"))
      (node (ref "E5") (pin "12") (pinfunction "I1_12") (pintype "input"))
      (node (ref "R3") (pin "1") (pinfunction "1_1") (pintype "passive"))
      (node (ref "R4") (pin "2") (pinfunction "2_2") (pintype "passive"))
    )
    (net (code "73") (name "Net-(E18A-I0)") (class "Default")
      (node (ref "E18") (pin "1") (pinfunction "I0_1") (pintype "input"))
      (node (ref "FIELDS") (pin "2") (pinfunction "2_2") (pintype "passive"))
    )
    (net (code "74") (name "Net-(E18A-I1)") (class "Default")
      (node (ref "E18") (pin "2") (pinfunction "I1_2") (pintype "input"))
      (node (ref "FIELDS") (pin "4") (pinfunction "4_4") (pintype "passive"))
    )
    (net (code "75") (name "Net-(E18A-I2)") (class "Default")
      (node (ref "E18") (pin "3") (pinfunction "I2_3") (pintype "input"))
      (node (ref "FIELDS") (pin "6") (pinfunction "6_6") (pintype "passive"))
    )
    (net (code "76") (name "Net-(E18A-I3)") (class "Default")
      (node (ref "E18") (pin "4") (pinfunction "I3_4") (pintype "input"))
      (node (ref "FIELDS") (pin "8") (pinfunction "8_8") (pintype "passive"))
    )
    (net (code "77") (name "Net-(E18A-I4)") (class "Default")
      (node (ref "E18") (pin "5") (pinfunction "I4_5") (pintype "input"))
      (node (ref "FIELDS") (pin "10") (pinfunction "10_10") (pintype "passive"))
    )
    (net (code "78") (name "Net-(E18A-I5)") (class "Default")
      (node (ref "E18") (pin "6") (pinfunction "I5_6") (pintype "input"))
      (node (ref "FIELDS") (pin "12") (pinfunction "12_12") (pintype "passive"))
    )
    (net (code "79") (name "Net-(E18A-I6)") (class "Default")
      (node (ref "E18") (pin "11") (pinfunction "I6_11") (pintype "input"))
      (node (ref "FIELDS") (pin "16") (pinfunction "16_16") (pintype "passive"))
    )
    (net (code "80") (name "Net-(E18A-I7)") (class "Default")
      (node (ref "E18") (pin "12") (pinfunction "I7_12") (pintype "input"))
      (node (ref "FIELDS") (pin "14") (pinfunction "14_14") (pintype "passive"))
    )
    (net (code "81") (name "Net-(E19A-Y0)") (class "Default")
      (node (ref "E19") (pin "15") (pinfunction "Y0_15") (pintype "output"))
      (node (ref "FIELDS") (pin "1") (pinfunction "1_1") (pintype "passive"))
    )
    (net (code "82") (name "Net-(E19A-Y1)") (class "Default")
      (node (ref "E19") (pin "14") (pinfunction "Y1_14") (pintype "output"))
      (node (ref "FIELDS") (pin "3") (pinfunction "3_3") (pintype "passive"))
    )
    (net (code "83") (name "Net-(E19A-Y2)") (class "Default")
      (node (ref "E19") (pin "13") (pinfunction "Y2_13") (pintype "output"))
      (node (ref "FIELDS") (pin "5") (pinfunction "5_5") (pintype "passive"))
    )
    (net (code "84") (name "Net-(E19A-Y3)") (class "Default")
      (node (ref "E19") (pin "12") (pinfunction "Y3_12") (pintype "output"))
      (node (ref "FIELDS") (pin "7") (pinfunction "7_7") (pintype "passive"))
    )
    (net (code "85") (name "Net-(E19A-Y4)") (class "Default")
      (node (ref "E19") (pin "11") (pinfunction "Y4_11") (pintype "output"))
      (node (ref "FIELDS") (pin "9") (pinfunction "9_9") (pintype "passive"))
    )
    (net (code "86") (name "Net-(E19A-Y5)") (class "Default")
      (node (ref "E19") (pin "10") (pinfunction "Y5_10") (pintype "output"))
      (node (ref "FIELDS") (pin "11") (pinfunction "11_11") (pintype "passive"))
    )
    (net (code "87") (name "Net-(E19A-Y6)") (class "Default")
      (node (ref "E19") (pin "9") (pinfunction "Y6_9") (pintype "output"))
      (node (ref "FIELDS") (pin "13") (pinfunction "13_13") (pintype "passive"))
    )
    (net (code "88") (name "Net-(E19A-Y7)") (class "Default")
      (node (ref "E19") (pin "7") (pinfunction "Y7_7") (pintype "output"))
      (node (ref "FIELDS") (pin "15") (pinfunction "15_15") (pintype "passive"))
    )
    (net (code "89") (name "OE(0)") (class "Default")
      (node (ref "E11") (pin "6") (pinfunction "~{Q}_6") (pintype "output"))
      (node (ref "E12") (pin "1") (pinfunction "G_1") (pintype "input"))
      (node (ref "E12") (pin "19") (pinfunction "G_19") (pintype "input"))
      (node (ref "E13") (pin "1") (pinfunction "G_1") (pintype "input"))
      (node (ref "E13") (pin "19") (pinfunction "G_19") (pintype "input"))
      (node (ref "E16") (pin "22") (pinfunction "~{OE}_22") (pintype "input"))
      (node (ref "E17") (pin "22") (pinfunction "~{OE}_22") (pintype "input"))
      (node (ref "SV2") (pin "22") (pinfunction "22_22") (pintype "passive"))
      (node (ref "SV4") (pin "22") (pinfunction "22_22") (pintype "passive"))
      (node (ref "SV5") (pin "22") (pinfunction "22_22") (pintype "passive"))
    )
    (net (code "90") (name "PARITY") (class "Default")
      (node (ref "E13") (pin "11") (pinfunction "A1_11") (pintype "input"))
      (node (ref "E13") (pin "13") (pinfunction "A2_13") (pintype "input"))
      (node (ref "E13") (pin "15") (pinfunction "A3_15") (pintype "input"))
      (node (ref "E13") (pin "17") (pinfunction "A4_17") (pintype "input"))
      (node (ref "E15") (pin "9") (pinfunction "Y1_9") (pintype "tri_state"))
      (node (ref "E16") (pin "16") (pinfunction "I/O4_16") (pintype "bidirectional"))
      (node (ref "SV2") (pin "3") (pinfunction "3_3") (pintype "passive"))
      (node (ref "SV3") (pin "3") (pinfunction "3_3") (pintype "passive"))
      (node (ref "SV4") (pin "3") (pinfunction "3_3") (pintype "passive"))
    )
    (net (code "91") (name "PWR_OK(0)") (class "Default")
      (node (ref "E5") (pin "13") (pinfunction "O_13") (pintype "open_collector"))
      (node (ref "R5") (pin "1") (pinfunction "1_1") (pintype "passive"))
      (node (ref "RESET") (pin "1") (pinfunction "1_1") (pintype "passive"))
    )
    (net (code "92") (name "RESET") (class "Default")
      (node (ref "E1") (pin "8") (pinfunction "O_8") (pintype "output"))
      (node (ref "E10") (pin "11") (pinfunction "CLK_11") (pintype "input"))
      (node (ref "E10") (pin "3") (pinfunction "CLK_3") (pintype "input"))
      (node (ref "E11") (pin "3") (pinfunction "CLK_3") (pintype "input"))
      (node (ref "E9") (pin "3") (pinfunction "CLK_3") (pintype "input"))
    )
    (net (code "93") (name "STROBE(0)") (class "Default")
      (node (ref "E5") (pin "4") (pinfunction "O_4") (pintype "open_collector"))
      (node (ref "H05") (pin "P2") (pinfunction "1_P2") (pintype "bidirectional"))
    )
    (net (code "94") (name "STROBE(1)") (class "Default")
      (node (ref "E10") (pin "5") (pinfunction "Q_5") (pintype "output"))
      (node (ref "E5") (pin "5") (pinfunction "I0_5") (pintype "input"))
      (node (ref "E5") (pin "6") (pinfunction "I1_6") (pintype "input"))
    )
    (net (code "95") (name "TP150") (class "Default")
      (node (ref "E10") (pin "10") (pinfunction "PRE_10") (pintype "input"))
      (node (ref "E8") (pin "6") (pinfunction "TAP3_6") (pintype "output"))
    )
    (net (code "96") (name "TP250") (class "Default")
      (node (ref "E7") (pin "1") (pinfunction "IN_1") (pintype "input"))
      (node (ref "E8") (pin "5") (pinfunction "TAP5_5") (pintype "output"))
    )
    (net (code "97") (name "TP300") (class "Default")
      (node (ref "E10") (pin "13") (pinfunction "CLR_13") (pintype "input"))
      (node (ref "E7") (pin "7") (pinfunction "TAP1_7") (pintype "output"))
    )
    (net (code "98") (name "TP500") (class "Default")
      (node (ref "E11") (pin "13") (pinfunction "CLR_13") (pintype "input"))
      (node (ref "E6") (pin "1") (pinfunction "IN_1") (pintype "input"))
      (node (ref "E7") (pin "5") (pinfunction "TAP5_5") (pintype "output"))
      (node (ref "E9") (pin "4") (pinfunction "PRE_4") (pintype "input"))
    )
    (net (code "99") (name "TP550") (class "Default")
      (node (ref "E6") (pin "7") (pinfunction "TAP1_7") (pintype "output"))
      (node (ref "E9") (pin "1") (pinfunction "CLR_1") (pintype "input"))
    )
    (net (code "100") (name "VCC") (class "Default")
      (node (ref "C10") (pin "1") (pinfunction "1_1") (pintype "passive"))
      (node (ref "C11") (pin "1") (pinfunction "1_1") (pintype "passive"))
      (node (ref "C12") (pin "1") (pinfunction "1_1") (pintype "passive"))
      (node (ref "C13") (pin "1") (pinfunction "1_1") (pintype "passive"))
      (node (ref "C14") (pin "1") (pinfunction "1_1") (pintype "passive"))
      (node (ref "C15") (pin "1") (pinfunction "1_1") (pintype "passive"))
      (node (ref "C16") (pin "1") (pinfunction "1_1") (pintype "passive"))
      (node (ref "C2") (pin "1") (pinfunction "1_1") (pintype "passive"))
      (node (ref "C3") (pin "1") (pinfunction "1_1") (pintype "passive"))
      (node (ref "C4") (pin "1") (pinfunction "1_1") (pintype "passive"))
      (node (ref "C5") (pin "1") (pinfunction "1_1") (pintype "passive"))
      (node (ref "C6") (pin "1") (pinfunction "1_1") (pintype "passive"))
      (node (ref "C7") (pin "1") (pinfunction "1_1") (pintype "passive"))
      (node (ref "C8") (pin "1") (pinfunction "1_1") (pintype "passive"))
      (node (ref "C9") (pin "1") (pinfunction "1_1") (pintype "passive"))
      (node (ref "E11") (pin "10") (pinfunction "PRE_10") (pintype "input"))
      (node (ref "E16") (pin "28") (pinfunction "VCC_28") (pintype "power_in"))
      (node (ref "E17") (pin "28") (pinfunction "VCC_28") (pintype "power_in"))
      (node (ref "E19") (pin "6") (pinfunction "G1_6") (pintype "input"))
      (node (ref "E5") (pin "8") (pinfunction "I0_8") (pintype "input"))
      (node (ref "E5") (pin "9") (pinfunction "I1_9") (pintype "input"))
      (node (ref "E9") (pin "10") (pinfunction "PRE_10") (pintype "input"))
      (node (ref "E9") (pin "11") (pinfunction "CLK_11") (pintype "input"))
      (node (ref "E9") (pin "12") (pinfunction "D_12") (pintype "input"))
      (node (ref "E9") (pin "13") (pinfunction "CLR_13") (pintype "input"))
      (node (ref "R3") (pin "2") (pinfunction "2_2") (pintype "passive"))
      (node (ref "R5") (pin "2") (pinfunction "2_2") (pintype "passive"))
      (node (ref "SV1") (pin "49") (pinfunction "49_49") (pintype "passive"))
      (node (ref "SV1") (pin "50") (pinfunction "50_50") (pintype "passive"))
      (node (ref "SV2") (pin "49") (pinfunction "49_49") (pintype "passive"))
      (node (ref "SV2") (pin "50") (pinfunction "50_50") (pintype "passive"))
      (node (ref "SV3") (pin "49") (pinfunction "49_49") (pintype "passive"))
      (node (ref "SV3") (pin "50") (pinfunction "50_50") (pintype "passive"))
      (node (ref "SV4") (pin "49") (pinfunction "49_49") (pintype "passive"))
      (node (ref "SV4") (pin "50") (pinfunction "50_50") (pintype "passive"))
      (node (ref "SV5") (pin "49") (pinfunction "49_49") (pintype "passive"))
      (node (ref "SV5") (pin "50") (pinfunction "50_50") (pintype "passive"))
      (node (ref "X1") (pin "1") (pinfunction "KL_1") (pintype "passive"))
    )
    (net (code "101") (name "WE(0)") (class "Default")
      (node (ref "E10") (pin "8") (pinfunction "~{Q}_8") (pintype "output"))
      (node (ref "E14") (pin "1") (pinfunction "G_1") (pintype "input"))
      (node (ref "E14") (pin "19") (pinfunction "G_19") (pintype "input"))
      (node (ref "E15") (pin "1") (pinfunction "G_1") (pintype "input"))
      (node (ref "E15") (pin "19") (pinfunction "G_19") (pintype "input"))
      (node (ref "E16") (pin "27") (pinfunction "~{WE}_27") (pintype "input"))
      (node (ref "E17") (pin "27") (pinfunction "~{WE}_27") (pintype "input"))
      (node (ref "SV2") (pin "32") (pinfunction "32_32") (pintype "passive"))
      (node (ref "SV3") (pin "32") (pinfunction "32_32") (pintype "passive"))
      (node (ref "SV5") (pin "32") (pinfunction "32_32") (pintype "passive"))
    )
    (net (code "102") (name "unconnected-(E2A-TAP1-Pad7)") (class "Default")
      (node (ref "E2") (pin "7") (pinfunction "TAP1_7") (pintype "output"))
    )
    (net (code "103") (name "unconnected-(E2A-TAP2-Pad2)") (class "Default")
      (node (ref "E2") (pin "2") (pinfunction "TAP2_2") (pintype "output"))
    )
    (net (code "104") (name "unconnected-(E2A-TAP4-Pad3)") (class "Default")
      (node (ref "E2") (pin "3") (pinfunction "TAP4_3") (pintype "output"))
    )
    (net (code "105") (name "unconnected-(E2A-TAP5-Pad5)") (class "Default")
      (node (ref "E2") (pin "5") (pinfunction "TAP5_5") (pintype "output"))
    )
    (net (code "106") (name "unconnected-(E3A-TAP1-Pad7)") (class "Default")
      (node (ref "E3") (pin "7") (pinfunction "TAP1_7") (pintype "output"))
    )
    (net (code "107") (name "unconnected-(E3A-TAP4-Pad3)") (class "Default")
      (node (ref "E3") (pin "3") (pinfunction "TAP4_3") (pintype "output"))
    )
    (net (code "108") (name "unconnected-(E4A-TAP1-Pad7)") (class "Default")
      (node (ref "E4") (pin "7") (pinfunction "TAP1_7") (pintype "output"))
    )
    (net (code "109") (name "unconnected-(E4A-TAP4-Pad3)") (class "Default")
      (node (ref "E4") (pin "3") (pinfunction "TAP4_3") (pintype "output"))
    )
    (net (code "110") (name "unconnected-(E5C-O-Pad10)") (class "Default")
      (node (ref "E5") (pin "10") (pinfunction "O_10") (pintype "open_collector"))
    )
    (net (code "111") (name "unconnected-(E6A-TAP2-Pad2)") (class "Default")
      (node (ref "E6") (pin "2") (pinfunction "TAP2_2") (pintype "output"))
    )
    (net (code "112") (name "unconnected-(E6A-TAP3-Pad6)") (class "Default")
      (node (ref "E6") (pin "6") (pinfunction "TAP3_6") (pintype "output"))
    )
    (net (code "113") (name "unconnected-(E6A-TAP4-Pad3)") (class "Default")
      (node (ref "E6") (pin "3") (pinfunction "TAP4_3") (pintype "output"))
    )
    (net (code "114") (name "unconnected-(E6A-TAP5-Pad5)") (class "Default")
      (node (ref "E6") (pin "5") (pinfunction "TAP5_5") (pintype "output"))
    )
    (net (code "115") (name "unconnected-(E7A-TAP2-Pad2)") (class "Default")
      (node (ref "E7") (pin "2") (pinfunction "TAP2_2") (pintype "output"))
    )
    (net (code "116") (name "unconnected-(E7A-TAP3-Pad6)") (class "Default")
      (node (ref "E7") (pin "6") (pinfunction "TAP3_6") (pintype "output"))
    )
    (net (code "117") (name "unconnected-(E7A-TAP4-Pad3)") (class "Default")
      (node (ref "E7") (pin "3") (pinfunction "TAP4_3") (pintype "output"))
    )
    (net (code "118") (name "unconnected-(E8A-TAP1-Pad7)") (class "Default")
      (node (ref "E8") (pin "7") (pinfunction "TAP1_7") (pintype "output"))
    )
    (net (code "119") (name "unconnected-(E8A-TAP2-Pad2)") (class "Default")
      (node (ref "E8") (pin "2") (pinfunction "TAP2_2") (pintype "output"))
    )
    (net (code "120") (name "unconnected-(E8A-TAP4-Pad3)") (class "Default")
      (node (ref "E8") (pin "3") (pinfunction "TAP4_3") (pintype "output"))
    )
    (net (code "121") (name "unconnected-(E9A-~{Q}-Pad6)") (class "Default")
      (node (ref "E9") (pin "6") (pinfunction "~{Q}_6") (pintype "output"))
    )
    (net (code "122") (name "unconnected-(E9B-Q-Pad9)") (class "Default")
      (node (ref "E9") (pin "9") (pinfunction "Q_9") (pintype "output"))
    )
    (net (code "123") (name "unconnected-(E9B-~{Q}-Pad8)") (class "Default")
      (node (ref "E9") (pin "8") (pinfunction "~{Q}_8") (pintype "output"))
    )
    (net (code "124") (name "unconnected-(E10A-~{Q}-Pad6)") (class "Default")
      (node (ref "E10") (pin "6") (pinfunction "~{Q}_6") (pintype "output"))
    )
    (net (code "125") (name "unconnected-(E10B-Q-Pad9)") (class "Default")
      (node (ref "E10") (pin "9") (pinfunction "Q_9") (pintype "output"))
    )
    (net (code "126") (name "unconnected-(E11A-Q-Pad5)") (class "Default")
      (node (ref "E11") (pin "5") (pinfunction "Q_5") (pintype "output"))
    )
    (net (code "127") (name "unconnected-(E11B-Q-Pad9)") (class "Default")
      (node (ref "E11") (pin "9") (pinfunction "Q_9") (pintype "output"))
    )
    (net (code "128") (name "unconnected-(E13B-Y2-Pad7)") (class "Default")
      (node (ref "E13") (pin "7") (pinfunction "Y2_7") (pintype "tri_state"))
    )
    (net (code "129") (name "unconnected-(E13B-Y3-Pad5)") (class "Default")
      (node (ref "E13") (pin "5") (pinfunction "Y3_5") (pintype "tri_state"))
    )
    (net (code "130") (name "unconnected-(E13B-Y4-Pad3)") (class "Default")
      (node (ref "E13") (pin "3") (pinfunction "Y4_3") (pintype "tri_state"))
    )
    (net (code "131") (name "unconnected-(E15B-Y2-Pad7)") (class "Default")
      (node (ref "E15") (pin "7") (pinfunction "Y2_7") (pintype "tri_state"))
    )
    (net (code "132") (name "unconnected-(E15B-Y3-Pad5)") (class "Default")
      (node (ref "E15") (pin "5") (pinfunction "Y3_5") (pintype "tri_state"))
    )
    (net (code "133") (name "unconnected-(E15B-Y4-Pad3)") (class "Default")
      (node (ref "E15") (pin "3") (pinfunction "Y4_3") (pintype "tri_state"))
    )
    (net (code "134") (name "unconnected-(E16-I{slash}O5-Pad17)") (class "Default")
      (node (ref "E16") (pin "17") (pinfunction "I/O5_17") (pintype "bidirectional"))
    )
    (net (code "135") (name "unconnected-(E16-I{slash}O6-Pad18)") (class "Default")
      (node (ref "E16") (pin "18") (pinfunction "I/O6_18") (pintype "bidirectional"))
    )
    (net (code "136") (name "unconnected-(E16-I{slash}O7-Pad19)") (class "Default")
      (node (ref "E16") (pin "19") (pinfunction "I/O7_19") (pintype "bidirectional"))
    )
    (net (code "137") (name "unconnected-(SV1-Pad3)") (class "Default")
      (node (ref "SV1") (pin "3") (pinfunction "3_3") (pintype "passive"))
    )
    (net (code "138") (name "unconnected-(SV1-Pad4)") (class "Default")
      (node (ref "SV1") (pin "4") (pinfunction "4_4") (pintype "passive"))
    )
    (net (code "139") (name "unconnected-(SV1-Pad5)") (class "Default")
      (node (ref "SV1") (pin "5") (pinfunction "5_5") (pintype "passive"))
    )
    (net (code "140") (name "unconnected-(SV1-Pad6)") (class "Default")
      (node (ref "SV1") (pin "6") (pinfunction "6_6") (pintype "passive"))
    )
    (net (code "141") (name "unconnected-(SV1-Pad7)") (class "Default")
      (node (ref "SV1") (pin "7") (pinfunction "7_7") (pintype "passive"))
    )
    (net (code "142") (name "unconnected-(SV1-Pad8)") (class "Default")
      (node (ref "SV1") (pin "8") (pinfunction "8_8") (pintype "passive"))
    )
    (net (code "143") (name "unconnected-(SV1-Pad9)") (class "Default")
      (node (ref "SV1") (pin "9") (pinfunction "9_9") (pintype "passive"))
    )
    (net (code "144") (name "unconnected-(SV1-Pad10)") (class "Default")
      (node (ref "SV1") (pin "10") (pinfunction "10_10") (pintype "passive"))
    )
    (net (code "145") (name "unconnected-(SV1-Pad11)") (class "Default")
      (node (ref "SV1") (pin "11") (pinfunction "11_11") (pintype "passive"))
    )
    (net (code "146") (name "unconnected-(SV1-Pad12)") (class "Default")
      (node (ref "SV1") (pin "12") (pinfunction "12_12") (pintype "passive"))
    )
    (net (code "147") (name "unconnected-(SV1-Pad13)") (class "Default")
      (node (ref "SV1") (pin "13") (pinfunction "13_13") (pintype "passive"))
    )
    (net (code "148") (name "unconnected-(SV1-Pad14)") (class "Default")
      (node (ref "SV1") (pin "14") (pinfunction "14_14") (pintype "passive"))
    )
    (net (code "149") (name "unconnected-(SV1-Pad15)") (class "Default")
      (node (ref "SV1") (pin "15") (pinfunction "15_15") (pintype "passive"))
    )
    (net (code "150") (name "unconnected-(SV1-Pad16)") (class "Default")
      (node (ref "SV1") (pin "16") (pinfunction "16_16") (pintype "passive"))
    )
    (net (code "151") (name "unconnected-(SV1-Pad17)") (class "Default")
      (node (ref "SV1") (pin "17") (pinfunction "17_17") (pintype "passive"))
    )
    (net (code "152") (name "unconnected-(SV1-Pad18)") (class "Default")
      (node (ref "SV1") (pin "18") (pinfunction "18_18") (pintype "passive"))
    )
    (net (code "153") (name "unconnected-(SV1-Pad19)") (class "Default")
      (node (ref "SV1") (pin "19") (pinfunction "19_19") (pintype "passive"))
    )
    (net (code "154") (name "unconnected-(SV1-Pad21)") (class "Default")
      (node (ref "SV1") (pin "21") (pinfunction "21_21") (pintype "passive"))
    )
    (net (code "155") (name "unconnected-(SV1-Pad22)") (class "Default")
      (node (ref "SV1") (pin "22") (pinfunction "22_22") (pintype "passive"))
    )
    (net (code "156") (name "unconnected-(SV1-Pad23)") (class "Default")
      (node (ref "SV1") (pin "23") (pinfunction "23_23") (pintype "passive"))
    )
    (net (code "157") (name "unconnected-(SV1-Pad25)") (class "Default")
      (node (ref "SV1") (pin "25") (pinfunction "25_25") (pintype "passive"))
    )
    (net (code "158") (name "unconnected-(SV1-Pad32)") (class "Default")
      (node (ref "SV1") (pin "32") (pinfunction "32_32") (pintype "passive"))
    )
    (net (code "159") (name "unconnected-(SV1-Pad35)") (class "Default")
      (node (ref "SV1") (pin "35") (pinfunction "35_35") (pintype "passive"))
    )
    (net (code "160") (name "unconnected-(SV1-Pad36)") (class "Default")
      (node (ref "SV1") (pin "36") (pinfunction "36_36") (pintype "passive"))
    )
    (net (code "161") (name "unconnected-(SV1-Pad37)") (class "Default")
      (node (ref "SV1") (pin "37") (pinfunction "37_37") (pintype "passive"))
    )
    (net (code "162") (name "unconnected-(SV1-Pad38)") (class "Default")
      (node (ref "SV1") (pin "38") (pinfunction "38_38") (pintype "passive"))
    )
    (net (code "163") (name "unconnected-(SV1-Pad39)") (class "Default")
      (node (ref "SV1") (pin "39") (pinfunction "39_39") (pintype "passive"))
    )
    (net (code "164") (name "unconnected-(SV1-Pad40)") (class "Default")
      (node (ref "SV1") (pin "40") (pinfunction "40_40") (pintype "passive"))
    )
    (net (code "165") (name "unconnected-(SV1-Pad41)") (class "Default")
      (node (ref "SV1") (pin "41") (pinfunction "41_41") (pintype "passive"))
    )
    (net (code "166") (name "unconnected-(SV1-Pad42)") (class "Default")
      (node (ref "SV1") (pin "42") (pinfunction "42_42") (pintype "passive"))
    )
    (net (code "167") (name "unconnected-(SV1-Pad45)") (class "Default")
      (node (ref "SV1") (pin "45") (pinfunction "45_45") (pintype "passive"))
    )
    (net (code "168") (name "unconnected-(SV1-Pad47)") (class "Default")
      (node (ref "SV1") (pin "47") (pinfunction "47_47") (pintype "passive"))
    )
    (net (code "169") (name "unconnected-(SV1-Pad48)") (class "Default")
      (node (ref "SV1") (pin "48") (pinfunction "48_48") (pintype "passive"))
    )
    (net (code "170") (name "unconnected-(SV2-Pad34)") (class "Default")
      (node (ref "SV2") (pin "34") (pinfunction "34_34") (pintype "passive"))
    )
    (net (code "171") (name "unconnected-(SV2-Pad37)") (class "Default")
      (node (ref "SV2") (pin "37") (pinfunction "37_37") (pintype "passive"))
    )
    (net (code "172") (name "unconnected-(SV2-Pad39)") (class "Default")
      (node (ref "SV2") (pin "39") (pinfunction "39_39") (pintype "passive"))
    )
    (net (code "173") (name "unconnected-(SV2-Pad40)") (class "Default")
      (node (ref "SV2") (pin "40") (pinfunction "40_40") (pintype "passive"))
    )
    (net (code "174") (name "unconnected-(SV2-Pad41)") (class "Default")
      (node (ref "SV2") (pin "41") (pinfunction "41_41") (pintype "passive"))
    )
    (net (code "175") (name "unconnected-(SV2-Pad42)") (class "Default")
      (node (ref "SV2") (pin "42") (pinfunction "42_42") (pintype "passive"))
    )
    (net (code "176") (name "unconnected-(SV2-Pad43)") (class "Default")
      (node (ref "SV2") (pin "43") (pinfunction "43_43") (pintype "passive"))
    )
    (net (code "177") (name "unconnected-(SV2-Pad44)") (class "Default")
      (node (ref "SV2") (pin "44") (pinfunction "44_44") (pintype "passive"))
    )
    (net (code "178") (name "unconnected-(SV2-Pad45)") (class "Default")
      (node (ref "SV2") (pin "45") (pinfunction "45_45") (pintype "passive"))
    )
    (net (code "179") (name "unconnected-(SV2-Pad46)") (class "Default")
      (node (ref "SV2") (pin "46") (pinfunction "46_46") (pintype "passive"))
    )
    (net (code "180") (name "unconnected-(SV2-Pad47)") (class "Default")
      (node (ref "SV2") (pin "47") (pinfunction "47_47") (pintype "passive"))
    )
    (net (code "181") (name "unconnected-(SV2-Pad48)") (class "Default")
      (node (ref "SV2") (pin "48") (pinfunction "48_48") (pintype "passive"))
    )
    (net (code "182") (name "unconnected-(SV3-Pad15)") (class "Default")
      (node (ref "SV3") (pin "15") (pinfunction "15_15") (pintype "passive"))
    )
    (net (code "183") (name "unconnected-(SV3-Pad17)") (class "Default")
      (node (ref "SV3") (pin "17") (pinfunction "17_17") (pintype "passive"))
    )
    (net (code "184") (name "unconnected-(SV3-Pad18)") (class "Default")
      (node (ref "SV3") (pin "18") (pinfunction "18_18") (pintype "passive"))
    )
    (net (code "185") (name "unconnected-(SV3-Pad19)") (class "Default")
      (node (ref "SV3") (pin "19") (pinfunction "19_19") (pintype "passive"))
    )
    (net (code "186") (name "unconnected-(SV3-Pad20)") (class "Default")
      (node (ref "SV3") (pin "20") (pinfunction "20_20") (pintype "passive"))
    )
    (net (code "187") (name "unconnected-(SV3-Pad21)") (class "Default")
      (node (ref "SV3") (pin "21") (pinfunction "21_21") (pintype "passive"))
    )
    (net (code "188") (name "unconnected-(SV3-Pad22)") (class "Default")
      (node (ref "SV3") (pin "22") (pinfunction "22_22") (pintype "passive"))
    )
    (net (code "189") (name "unconnected-(SV3-Pad23)") (class "Default")
      (node (ref "SV3") (pin "23") (pinfunction "23_23") (pintype "passive"))
    )
    (net (code "190") (name "unconnected-(SV3-Pad24)") (class "Default")
      (node (ref "SV3") (pin "24") (pinfunction "24_24") (pintype "passive"))
    )
    (net (code "191") (name "unconnected-(SV3-Pad25)") (class "Default")
      (node (ref "SV3") (pin "25") (pinfunction "25_25") (pintype "passive"))
    )
    (net (code "192") (name "unconnected-(SV3-Pad26)") (class "Default")
      (node (ref "SV3") (pin "26") (pinfunction "26_26") (pintype "passive"))
    )
    (net (code "193") (name "unconnected-(SV3-Pad27)") (class "Default")
      (node (ref "SV3") (pin "27") (pinfunction "27_27") (pintype "passive"))
    )
    (net (code "194") (name "unconnected-(SV3-Pad28)") (class "Default")
      (node (ref "SV3") (pin "28") (pinfunction "28_28") (pintype "passive"))
    )
    (net (code "195") (name "unconnected-(SV3-Pad29)") (class "Default")
      (node (ref "SV3") (pin "29") (pinfunction "29_29") (pintype "passive"))
    )
    (net (code "196") (name "unconnected-(SV3-Pad34)") (class "Default")
      (node (ref "SV3") (pin "34") (pinfunction "34_34") (pintype "passive"))
    )
    (net (code "197") (name "unconnected-(SV3-Pad37)") (class "Default")
      (node (ref "SV3") (pin "37") (pinfunction "37_37") (pintype "passive"))
    )
    (net (code "198") (name "unconnected-(SV3-Pad39)") (class "Default")
      (node (ref "SV3") (pin "39") (pinfunction "39_39") (pintype "passive"))
    )
    (net (code "199") (name "unconnected-(SV3-Pad40)") (class "Default")
      (node (ref "SV3") (pin "40") (pinfunction "40_40") (pintype "passive"))
    )
    (net (code "200") (name "unconnected-(SV3-Pad41)") (class "Default")
      (node (ref "SV3") (pin "41") (pinfunction "41_41") (pintype "passive"))
    )
    (net (code "201") (name "unconnected-(SV3-Pad45)") (class "Default")
      (node (ref "SV3") (pin "45") (pinfunction "45_45") (pintype "passive"))
    )
    (net (code "202") (name "unconnected-(SV3-Pad47)") (class "Default")
      (node (ref "SV3") (pin "47") (pinfunction "47_47") (pintype "passive"))
    )
    (net (code "203") (name "unconnected-(SV3-Pad48)") (class "Default")
      (node (ref "SV3") (pin "48") (pinfunction "48_48") (pintype "passive"))
    )
    (net (code "204") (name "unconnected-(SV4-Pad15)") (class "Default")
      (node (ref "SV4") (pin "15") (pinfunction "15_15") (pintype "passive"))
    )
    (net (code "205") (name "unconnected-(SV4-Pad17)") (class "Default")
      (node (ref "SV4") (pin "17") (pinfunction "17_17") (pintype "passive"))
    )
    (net (code "206") (name "unconnected-(SV4-Pad18)") (class "Default")
      (node (ref "SV4") (pin "18") (pinfunction "18_18") (pintype "passive"))
    )
    (net (code "207") (name "unconnected-(SV4-Pad19)") (class "Default")
      (node (ref "SV4") (pin "19") (pinfunction "19_19") (pintype "passive"))
    )
    (net (code "208") (name "unconnected-(SV4-Pad20)") (class "Default")
      (node (ref "SV4") (pin "20") (pinfunction "20_20") (pintype "passive"))
    )
    (net (code "209") (name "unconnected-(SV4-Pad21)") (class "Default")
      (node (ref "SV4") (pin "21") (pinfunction "21_21") (pintype "passive"))
    )
    (net (code "210") (name "unconnected-(SV4-Pad23)") (class "Default")
      (node (ref "SV4") (pin "23") (pinfunction "23_23") (pintype "passive"))
    )
    (net (code "211") (name "unconnected-(SV4-Pad24)") (class "Default")
      (node (ref "SV4") (pin "24") (pinfunction "24_24") (pintype "passive"))
    )
    (net (code "212") (name "unconnected-(SV4-Pad25)") (class "Default")
      (node (ref "SV4") (pin "25") (pinfunction "25_25") (pintype "passive"))
    )
    (net (code "213") (name "unconnected-(SV4-Pad26)") (class "Default")
      (node (ref "SV4") (pin "26") (pinfunction "26_26") (pintype "passive"))
    )
    (net (code "214") (name "unconnected-(SV4-Pad27)") (class "Default")
      (node (ref "SV4") (pin "27") (pinfunction "27_27") (pintype "passive"))
    )
    (net (code "215") (name "unconnected-(SV4-Pad28)") (class "Default")
      (node (ref "SV4") (pin "28") (pinfunction "28_28") (pintype "passive"))
    )
    (net (code "216") (name "unconnected-(SV4-Pad29)") (class "Default")
      (node (ref "SV4") (pin "29") (pinfunction "29_29") (pintype "passive"))
    )
    (net (code "217") (name "unconnected-(SV4-Pad30)") (class "Default")
      (node (ref "SV4") (pin "30") (pinfunction "30_30") (pintype "passive"))
    )
    (net (code "218") (name "unconnected-(SV4-Pad31)") (class "Default")
      (node (ref "SV4") (pin "31") (pinfunction "31_31") (pintype "passive"))
    )
    (net (code "219") (name "unconnected-(SV4-Pad32)") (class "Default")
      (node (ref "SV4") (pin "32") (pinfunction "32_32") (pintype "passive"))
    )
    (net (code "220") (name "unconnected-(SV4-Pad33)") (class "Default")
      (node (ref "SV4") (pin "33") (pinfunction "33_33") (pintype "passive"))
    )
    (net (code "221") (name "unconnected-(SV4-Pad34)") (class "Default")
      (node (ref "SV4") (pin "34") (pinfunction "34_34") (pintype "passive"))
    )
    (net (code "222") (name "unconnected-(SV4-Pad35)") (class "Default")
      (node (ref "SV4") (pin "35") (pinfunction "35_35") (pintype "passive"))
    )
    (net (code "223") (name "unconnected-(SV4-Pad36)") (class "Default")
      (node (ref "SV4") (pin "36") (pinfunction "36_36") (pintype "passive"))
    )
    (net (code "224") (name "unconnected-(SV4-Pad38)") (class "Default")
      (node (ref "SV4") (pin "38") (pinfunction "38_38") (pintype "passive"))
    )
    (net (code "225") (name "unconnected-(SV4-Pad42)") (class "Default")
      (node (ref "SV4") (pin "42") (pinfunction "42_42") (pintype "passive"))
    )
    (net (code "226") (name "unconnected-(SV4-Pad43)") (class "Default")
      (node (ref "SV4") (pin "43") (pinfunction "43_43") (pintype "passive"))
    )
    (net (code "227") (name "unconnected-(SV4-Pad44)") (class "Default")
      (node (ref "SV4") (pin "44") (pinfunction "44_44") (pintype "passive"))
    )
    (net (code "228") (name "unconnected-(SV4-Pad45)") (class "Default")
      (node (ref "SV4") (pin "45") (pinfunction "45_45") (pintype "passive"))
    )
    (net (code "229") (name "unconnected-(SV4-Pad46)") (class "Default")
      (node (ref "SV4") (pin "46") (pinfunction "46_46") (pintype "passive"))
    )
    (net (code "230") (name "unconnected-(SV4-Pad47)") (class "Default")
      (node (ref "SV4") (pin "47") (pinfunction "47_47") (pintype "passive"))
    )
    (net (code "231") (name "unconnected-(SV4-Pad48)") (class "Default")
      (node (ref "SV4") (pin "48") (pinfunction "48_48") (pintype "passive"))
    )
    (net (code "232") (name "unconnected-(SV5-Pad3)") (class "Default")
      (node (ref "SV5") (pin "3") (pinfunction "3_3") (pintype "passive"))
    )
    (net (code "233") (name "unconnected-(SV5-Pad4)") (class "Default")
      (node (ref "SV5") (pin "4") (pinfunction "4_4") (pintype "passive"))
    )
    (net (code "234") (name "unconnected-(SV5-Pad5)") (class "Default")
      (node (ref "SV5") (pin "5") (pinfunction "5_5") (pintype "passive"))
    )
    (net (code "235") (name "unconnected-(SV5-Pad6)") (class "Default")
      (node (ref "SV5") (pin "6") (pinfunction "6_6") (pintype "passive"))
    )
    (net (code "236") (name "unconnected-(SV5-Pad7)") (class "Default")
      (node (ref "SV5") (pin "7") (pinfunction "7_7") (pintype "passive"))
    )
    (net (code "237") (name "unconnected-(SV5-Pad8)") (class "Default")
      (node (ref "SV5") (pin "8") (pinfunction "8_8") (pintype "passive"))
    )
    (net (code "238") (name "unconnected-(SV5-Pad9)") (class "Default")
      (node (ref "SV5") (pin "9") (pinfunction "9_9") (pintype "passive"))
    )
    (net (code "239") (name "unconnected-(SV5-Pad10)") (class "Default")
      (node (ref "SV5") (pin "10") (pinfunction "10_10") (pintype "passive"))
    )
    (net (code "240") (name "unconnected-(SV5-Pad11)") (class "Default")
      (node (ref "SV5") (pin "11") (pinfunction "11_11") (pintype "passive"))
    )
    (net (code "241") (name "unconnected-(SV5-Pad12)") (class "Default")
      (node (ref "SV5") (pin "12") (pinfunction "12_12") (pintype "passive"))
    )
    (net (code "242") (name "unconnected-(SV5-Pad13)") (class "Default")
      (node (ref "SV5") (pin "13") (pinfunction "13_13") (pintype "passive"))
    )
    (net (code "243") (name "unconnected-(SV5-Pad14)") (class "Default")
      (node (ref "SV5") (pin "14") (pinfunction "14_14") (pintype "passive"))
    )
    (net (code "244") (name "unconnected-(SV5-Pad15)") (class "Default")
      (node (ref "SV5") (pin "15") (pinfunction "15_15") (pintype "passive"))
    )
    (net (code "245") (name "unconnected-(SV5-Pad16)") (class "Default")
      (node (ref "SV5") (pin "16") (pinfunction "16_16") (pintype "passive"))
    )
    (net (code "246") (name "unconnected-(SV5-Pad17)") (class "Default")
      (node (ref "SV5") (pin "17") (pinfunction "17_17") (pintype "passive"))
    )
    (net (code "247") (name "unconnected-(SV5-Pad19)") (class "Default")
      (node (ref "SV5") (pin "19") (pinfunction "19_19") (pintype "passive"))
    )
    (net (code "248") (name "unconnected-(SV5-Pad20)") (class "Default")
      (node (ref "SV5") (pin "20") (pinfunction "20_20") (pintype "passive"))
    )
    (net (code "249") (name "unconnected-(SV5-Pad21)") (class "Default")
      (node (ref "SV5") (pin "21") (pinfunction "21_21") (pintype "passive"))
    )
    (net (code "250") (name "unconnected-(SV5-Pad23)") (class "Default")
      (node (ref "SV5") (pin "23") (pinfunction "23_23") (pintype "passive"))
    )
    (net (code "251") (name "unconnected-(SV5-Pad24)") (class "Default")
      (node (ref "SV5") (pin "24") (pinfunction "24_24") (pintype "passive"))
    )
    (net (code "252") (name "unconnected-(SV5-Pad25)") (class "Default")
      (node (ref "SV5") (pin "25") (pinfunction "25_25") (pintype "passive"))
    )
    (net (code "253") (name "unconnected-(SV5-Pad26)") (class "Default")
      (node (ref "SV5") (pin "26") (pinfunction "26_26") (pintype "passive"))
    )
    (net (code "254") (name "unconnected-(SV5-Pad27)") (class "Default")
      (node (ref "SV5") (pin "27") (pinfunction "27_27") (pintype "passive"))
    )
    (net (code "255") (name "unconnected-(SV5-Pad28)") (class "Default")
      (node (ref "SV5") (pin "28") (pinfunction "28_28") (pintype "passive"))
    )
    (net (code "256") (name "unconnected-(SV5-Pad29)") (class "Default")
      (node (ref "SV5") (pin "29") (pinfunction "29_29") (pintype "passive"))
    )
    (net (code "257") (name "unconnected-(SV5-Pad30)") (class "Default")
      (node (ref "SV5") (pin "30") (pinfunction "30_30") (pintype "passive"))
    )
    (net (code "258") (name "unconnected-(SV5-Pad31)") (class "Default")
      (node (ref "SV5") (pin "31") (pinfunction "31_31") (pintype "passive"))
    )
    (net (code "259") (name "unconnected-(SV5-Pad33)") (class "Default")
      (node (ref "SV5") (pin "33") (pinfunction "33_33") (pintype "passive"))
    )
    (net (code "260") (name "unconnected-(SV5-Pad35)") (class "Default")
      (node (ref "SV5") (pin "35") (pinfunction "35_35") (pintype "passive"))
    )
    (net (code "261") (name "unconnected-(SV5-Pad36)") (class "Default")
      (node (ref "SV5") (pin "36") (pinfunction "36_36") (pintype "passive"))
    )
    (net (code "262") (name "unconnected-(SV5-Pad38)") (class "Default")
      (node (ref "SV5") (pin "38") (pinfunction "38_38") (pintype "passive"))
    )
    (net (code "263") (name "unconnected-(SV5-Pad43)") (class "Default")
      (node (ref "SV5") (pin "43") (pinfunction "43_43") (pintype "passive"))
    )
    (net (code "264") (name "unconnected-(SV5-Pad44)") (class "Default")
      (node (ref "SV5") (pin "44") (pinfunction "44_44") (pintype "passive"))
    )
    (net (code "265") (name "unconnected-(SV5-Pad45)") (class "Default")
      (node (ref "SV5") (pin "45") (pinfunction "45_45") (pintype "passive"))
    )
    (net (code "266") (name "unconnected-(SV5-Pad46)") (class "Default")
      (node (ref "SV5") (pin "46") (pinfunction "46_46") (pintype "passive"))
    )
    (net (code "267") (name "unconnected-(SV5-Pad47)") (class "Default")
      (node (ref "SV5") (pin "47") (pinfunction "47_47") (pintype "passive"))
    )
    (net (code "268") (name "unconnected-(SV5-Pad48)") (class "Default")
      (node (ref "SV5") (pin "48") (pinfunction "48_48") (pintype "passive"))
    )
  )
)
